# bbb_audio_decoder.net
KiCad netlist of a schematic drawn in EAGLE
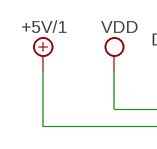
[diagram p0: schematic, sheet 1, part 1 of 2]
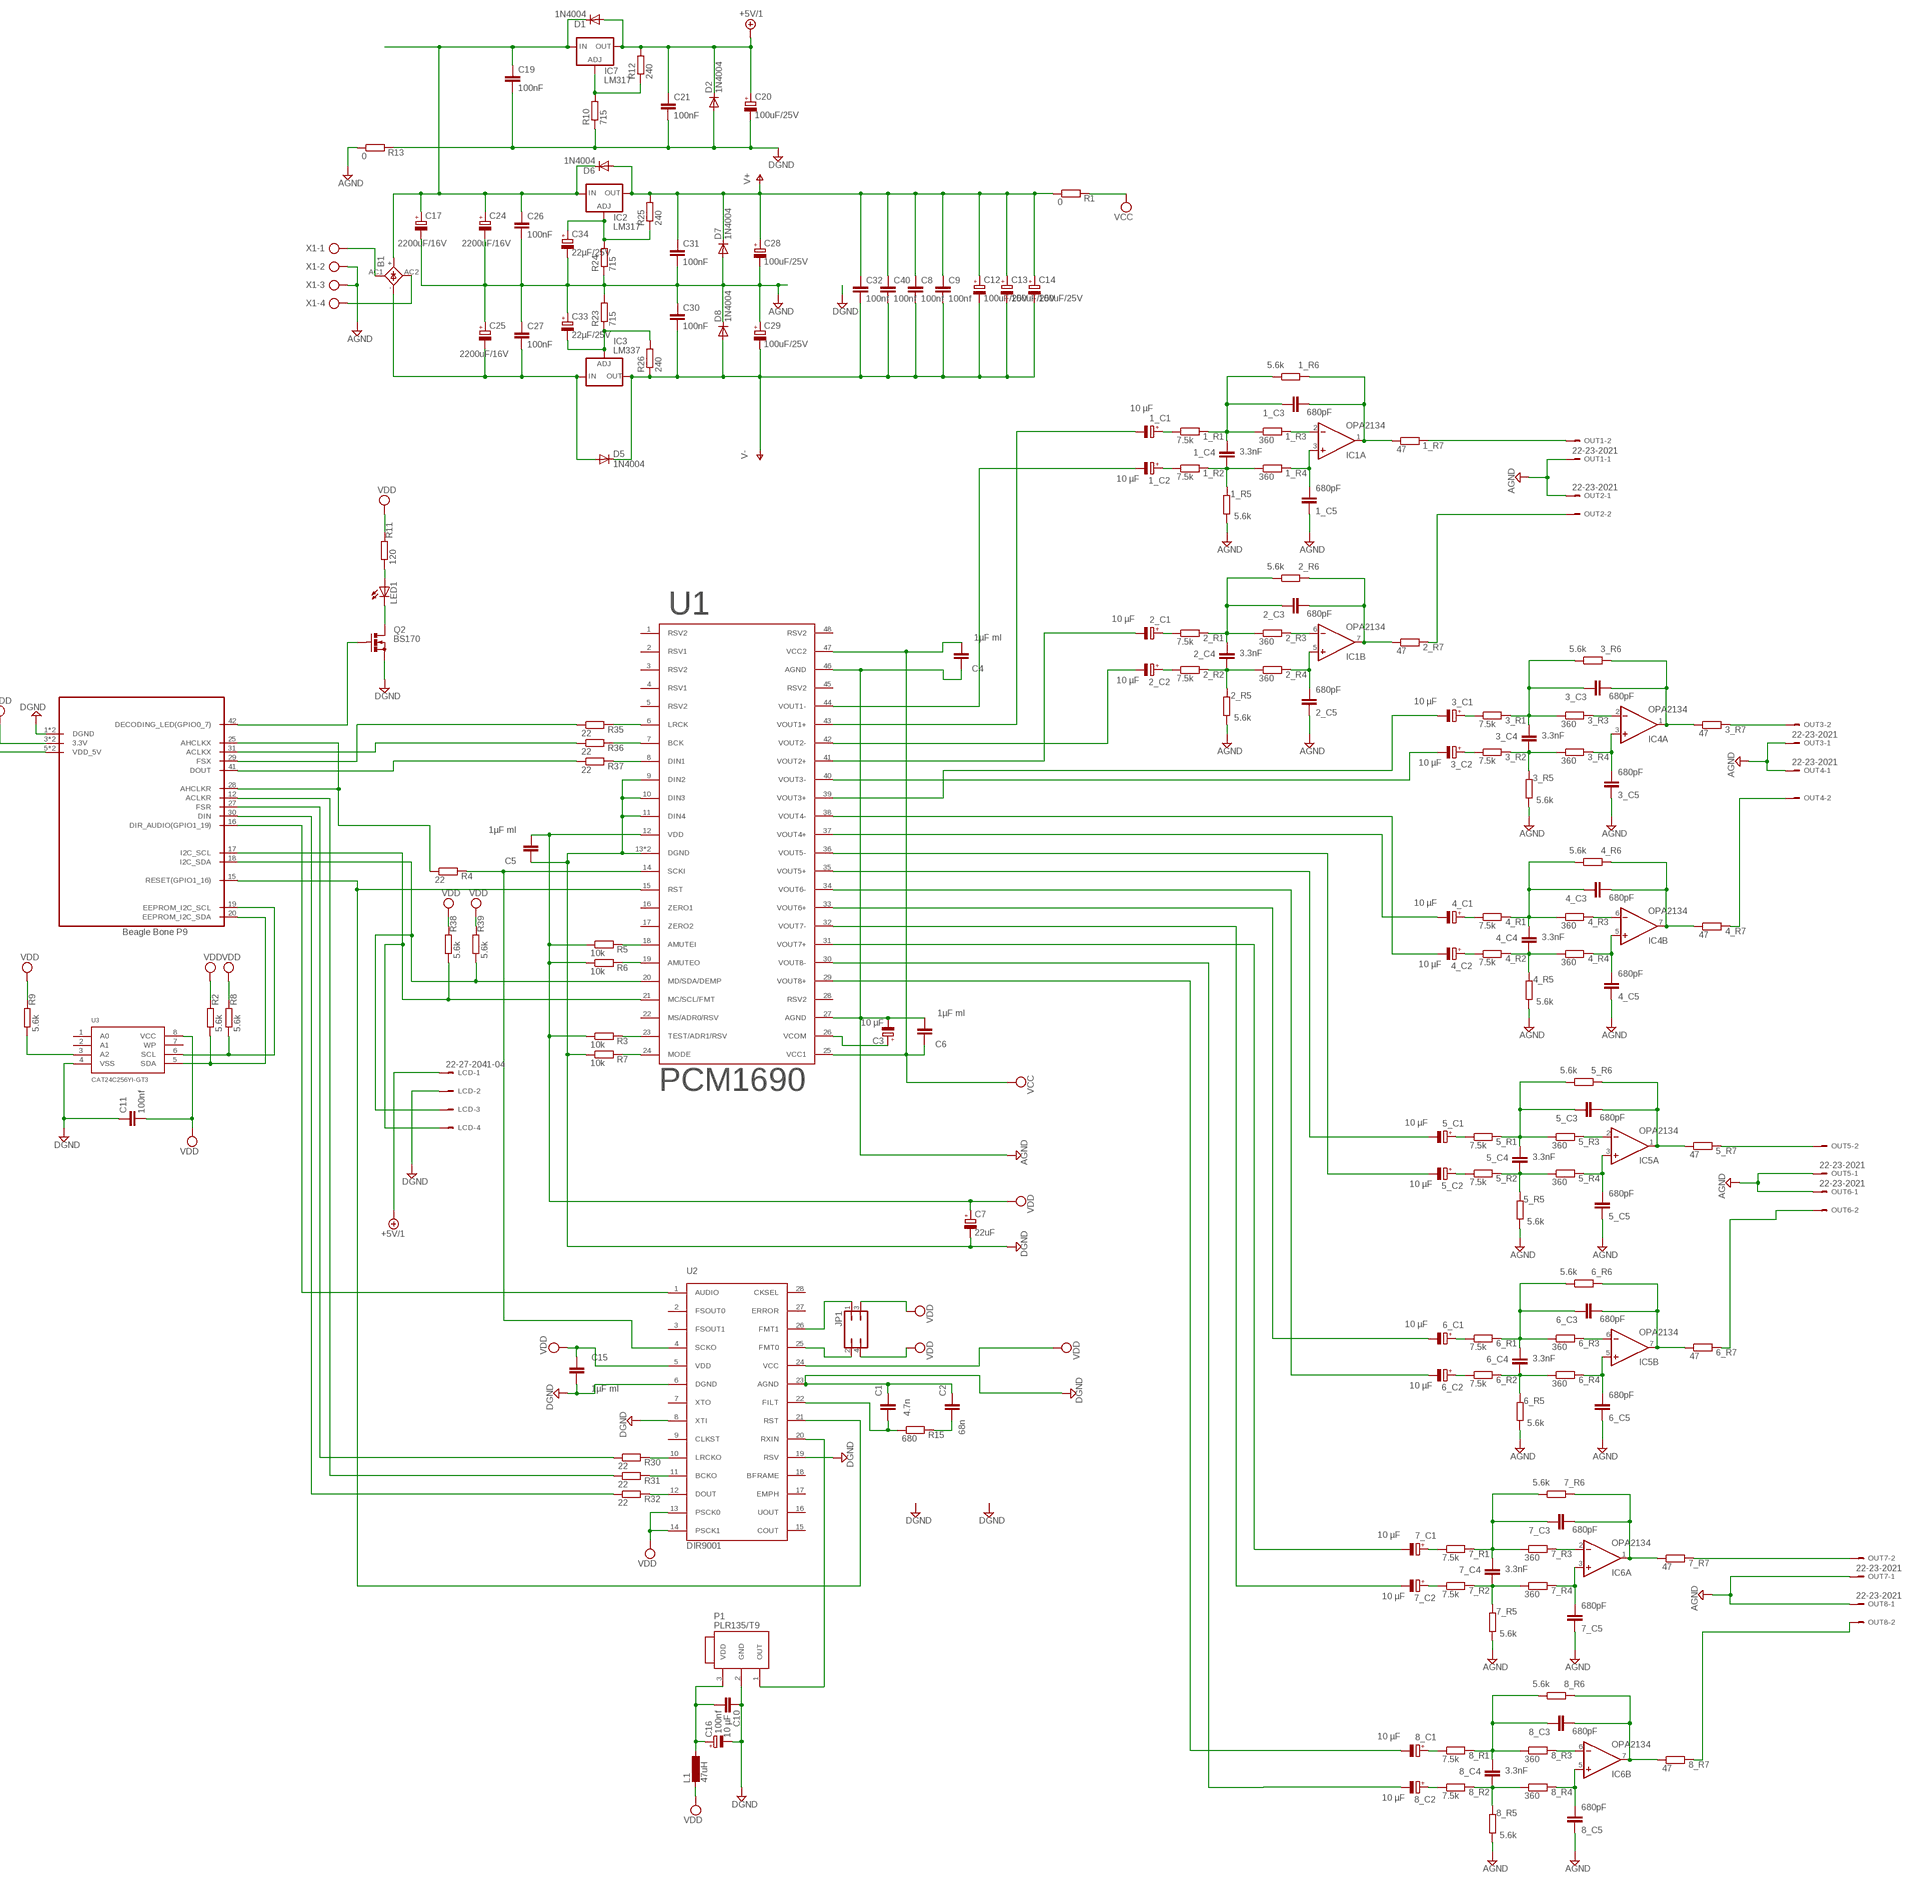
[diagram p1: schematic, sheet 1, part 2 of 2]

(export (version "E")
  (design (tool "Eeschema 10.0.6"))
  (components
    (comp (ref "1_C1")
      (value "10 µF")
      (footprint "eagle-import:E2-5")
      (libsource (lib "eagle-import") (part "CPOL-EUE2-5"))
    )
    (comp (ref "1_C2")
      (value "10 µF")
      (footprint "eagle-import:E2-5")
      (libsource (lib "eagle-import") (part "CPOL-EUE2-5"))
    )
    (comp (ref "1_C3")
      (value "680pF")
      (footprint "eagle-import:C050-024X044")
      (libsource (lib "eagle-import") (part "C-EU050-024X044"))
    )
    (comp (ref "1_C4")
      (value "3.3nF")
      (footprint "eagle-import:C050-025X075")
      (libsource (lib "eagle-import") (part "C-EU050-025X075"))
    )
    (comp (ref "1_C5")
      (value "680pF")
      (footprint "eagle-import:C050-024X044")
      (libsource (lib "eagle-import") (part "C-EU050-024X044"))
    )
    (comp (ref "1_R1")
      (value "7.5k")
      (footprint "eagle-import:0207_7")
      (libsource (lib "eagle-import") (part "R-EU_0207/7"))
    )
    (comp (ref "1_R2")
      (value "7.5k")
      (footprint "eagle-import:0207_7")
      (libsource (lib "eagle-import") (part "R-EU_0207/7"))
    )
    (comp (ref "1_R3")
      (value "360")
      (footprint "eagle-import:0207_7")
      (libsource (lib "eagle-import") (part "R-EU_0207/7"))
    )
    (comp (ref "1_R4")
      (value "360")
      (footprint "eagle-import:0207_7")
      (libsource (lib "eagle-import") (part "R-EU_0207/7"))
    )
    (comp (ref "1_R5")
      (value "5.6k")
      (footprint "eagle-import:0207_7")
      (libsource (lib "eagle-import") (part "R-EU_0207/7"))
    )
    (comp (ref "1_R6")
      (value "5.6k")
      (footprint "eagle-import:0207_7")
      (libsource (lib "eagle-import") (part "R-EU_0207/7"))
    )
    (comp (ref "1_R7")
      (value "47")
      (footprint "eagle-import:0207_7")
      (libsource (lib "eagle-import") (part "R-EU_0207/7"))
    )
    (comp (ref "2_C1")
      (value "10 µF")
      (footprint "eagle-import:E2-5")
      (libsource (lib "eagle-import") (part "CPOL-EUE2-5"))
    )
    (comp (ref "2_C2")
      (value "10 µF")
      (footprint "eagle-import:E2-5")
      (libsource (lib "eagle-import") (part "CPOL-EUE2-5"))
    )
    (comp (ref "2_C3")
      (value "680pF")
      (footprint "eagle-import:C050-024X044")
      (libsource (lib "eagle-import") (part "C-EU050-024X044"))
    )
    (comp (ref "2_C4")
      (value "3.3nF")
      (footprint "eagle-import:C050-025X075")
      (libsource (lib "eagle-import") (part "C-EU050-025X075"))
    )
    (comp (ref "2_C5")
      (value "680pF")
      (footprint "eagle-import:C050-024X044")
      (libsource (lib "eagle-import") (part "C-EU050-024X044"))
    )
    (comp (ref "2_R1")
      (value "7.5k")
      (footprint "eagle-import:0207_7")
      (libsource (lib "eagle-import") (part "R-EU_0207/7"))
    )
    (comp (ref "2_R2")
      (value "7.5k")
      (footprint "eagle-import:0207_7")
      (libsource (lib "eagle-import") (part "R-EU_0207/7"))
    )
    (comp (ref "2_R3")
      (value "360")
      (footprint "eagle-import:0207_7")
      (libsource (lib "eagle-import") (part "R-EU_0207/7"))
    )
    (comp (ref "2_R4")
      (value "360")
      (footprint "eagle-import:0207_7")
      (libsource (lib "eagle-import") (part "R-EU_0207/7"))
    )
    (comp (ref "2_R5")
      (value "5.6k")
      (footprint "eagle-import:0207_7")
      (libsource (lib "eagle-import") (part "R-EU_0207/7"))
    )
    (comp (ref "2_R6")
      (value "5.6k")
      (footprint "eagle-import:0207_7")
      (libsource (lib "eagle-import") (part "R-EU_0207/7"))
    )
    (comp (ref "2_R7")
      (value "47")
      (footprint "eagle-import:0207_7")
      (libsource (lib "eagle-import") (part "R-EU_0207/7"))
    )
    (comp (ref "3_C1")
      (value "10 µF")
      (footprint "eagle-import:E2-5")
      (libsource (lib "eagle-import") (part "CPOL-EUE2-5"))
    )
    (comp (ref "3_C2")
      (value "10 µF")
      (footprint "eagle-import:E2-5")
      (libsource (lib "eagle-import") (part "CPOL-EUE2-5"))
    )
    (comp (ref "3_C3")
      (value "680pF")
      (footprint "eagle-import:C050-024X044")
      (libsource (lib "eagle-import") (part "C-EU050-024X044"))
    )
    (comp (ref "3_C4")
      (value "3.3nF")
      (footprint "eagle-import:C050-025X075")
      (libsource (lib "eagle-import") (part "C-EU050-025X075"))
    )
    (comp (ref "3_C5")
      (value "680pF")
      (footprint "eagle-import:C050-024X044")
      (libsource (lib "eagle-import") (part "C-EU050-024X044"))
    )
    (comp (ref "3_R1")
      (value "7.5k")
      (footprint "eagle-import:0207_7")
      (libsource (lib "eagle-import") (part "R-EU_0207/7"))
    )
    (comp (ref "3_R2")
      (value "7.5k")
      (footprint "eagle-import:0207_7")
      (libsource (lib "eagle-import") (part "R-EU_0207/7"))
    )
    (comp (ref "3_R3")
      (value "360")
      (footprint "eagle-import:0207_7")
      (libsource (lib "eagle-import") (part "R-EU_0207/7"))
    )
    (comp (ref "3_R4")
      (value "360")
      (footprint "eagle-import:0207_7")
      (libsource (lib "eagle-import") (part "R-EU_0207/7"))
    )
    (comp (ref "3_R5")
      (value "5.6k")
      (footprint "eagle-import:0207_7")
      (libsource (lib "eagle-import") (part "R-EU_0207/7"))
    )
    (comp (ref "3_R6")
      (value "5.6k")
      (footprint "eagle-import:0207_7")
      (libsource (lib "eagle-import") (part "R-EU_0207/7"))
    )
    (comp (ref "3_R7")
      (value "47")
      (footprint "eagle-import:0207_7")
      (libsource (lib "eagle-import") (part "R-EU_0207/7"))
    )
    (comp (ref "4_C1")
      (value "10 µF")
      (footprint "eagle-import:E2-5")
      (libsource (lib "eagle-import") (part "CPOL-EUE2-5"))
    )
    (comp (ref "4_C2")
      (value "10 µF")
      (footprint "eagle-import:E2-5")
      (libsource (lib "eagle-import") (part "CPOL-EUE2-5"))
    )
    (comp (ref "4_C3")
      (value "680pF")
      (footprint "eagle-import:C050-024X044")
      (libsource (lib "eagle-import") (part "C-EU050-024X044"))
    )
    (comp (ref "4_C4")
      (value "3.3nF")
      (footprint "eagle-import:C050-025X075")
      (libsource (lib "eagle-import") (part "C-EU050-025X075"))
    )
    (comp (ref "4_C5")
      (value "680pF")
      (footprint "eagle-import:C050-024X044")
      (libsource (lib "eagle-import") (part "C-EU050-024X044"))
    )
    (comp (ref "4_R1")
      (value "7.5k")
      (footprint "eagle-import:0207_7")
      (libsource (lib "eagle-import") (part "R-EU_0207/7"))
    )
    (comp (ref "4_R2")
      (value "7.5k")
      (footprint "eagle-import:0207_7")
      (libsource (lib "eagle-import") (part "R-EU_0207/7"))
    )
    (comp (ref "4_R3")
      (value "360")
      (footprint "eagle-import:0207_7")
      (libsource (lib "eagle-import") (part "R-EU_0207/7"))
    )
    (comp (ref "4_R4")
      (value "360")
      (footprint "eagle-import:0207_7")
      (libsource (lib "eagle-import") (part "R-EU_0207/7"))
    )
    (comp (ref "4_R5")
      (value "5.6k")
      (footprint "eagle-import:0207_7")
      (libsource (lib "eagle-import") (part "R-EU_0207/7"))
    )
    (comp (ref "4_R6")
      (value "5.6k")
      (footprint "eagle-import:0207_7")
      (libsource (lib "eagle-import") (part "R-EU_0207/7"))
    )
    (comp (ref "4_R7")
      (value "47")
      (footprint "eagle-import:0207_7")
      (libsource (lib "eagle-import") (part "R-EU_0207/7"))
    )
    (comp (ref "5_C1")
      (value "10 µF")
      (footprint "eagle-import:E2-5")
      (libsource (lib "eagle-import") (part "CPOL-EUE2-5"))
    )
    (comp (ref "5_C2")
      (value "10 µF")
      (footprint "eagle-import:E2-5")
      (libsource (lib "eagle-import") (part "CPOL-EUE2-5"))
    )
    (comp (ref "5_C3")
      (value "680pF")
      (footprint "eagle-import:C050-024X044")
      (libsource (lib "eagle-import") (part "C-EU050-024X044"))
    )
    (comp (ref "5_C4")
      (value "3.3nF")
      (footprint "eagle-import:C050-025X075")
      (libsource (lib "eagle-import") (part "C-EU050-025X075"))
    )
    (comp (ref "5_C5")
      (value "680pF")
      (footprint "eagle-import:C050-024X044")
      (libsource (lib "eagle-import") (part "C-EU050-024X044"))
    )
    (comp (ref "5_R1")
      (value "7.5k")
      (footprint "eagle-import:0207_7")
      (libsource (lib "eagle-import") (part "R-EU_0207/7"))
    )
    (comp (ref "5_R2")
      (value "7.5k")
      (footprint "eagle-import:0207_7")
      (libsource (lib "eagle-import") (part "R-EU_0207/7"))
    )
    (comp (ref "5_R3")
      (value "360")
      (footprint "eagle-import:0207_7")
      (libsource (lib "eagle-import") (part "R-EU_0207/7"))
    )
    (comp (ref "5_R4")
      (value "360")
      (footprint "eagle-import:0207_7")
      (libsource (lib "eagle-import") (part "R-EU_0207/7"))
    )
    (comp (ref "5_R5")
      (value "5.6k")
      (footprint "eagle-import:0207_7")
      (libsource (lib "eagle-import") (part "R-EU_0207/7"))
    )
    (comp (ref "5_R6")
      (value "5.6k")
      (footprint "eagle-import:0207_7")
      (libsource (lib "eagle-import") (part "R-EU_0207/7"))
    )
    (comp (ref "5_R7")
      (value "47")
      (footprint "eagle-import:0207_7")
      (libsource (lib "eagle-import") (part "R-EU_0207/7"))
    )
    (comp (ref "6_C1")
      (value "10 µF")
      (footprint "eagle-import:E2-5")
      (libsource (lib "eagle-import") (part "CPOL-EUE2-5"))
    )
    (comp (ref "6_C2")
      (value "10 µF")
      (footprint "eagle-import:E2-5")
      (libsource (lib "eagle-import") (part "CPOL-EUE2-5"))
    )
    (comp (ref "6_C3")
      (value "680pF")
      (footprint "eagle-import:C050-024X044")
      (libsource (lib "eagle-import") (part "C-EU050-024X044"))
    )
    (comp (ref "6_C4")
      (value "3.3nF")
      (footprint "eagle-import:C050-025X075")
      (libsource (lib "eagle-import") (part "C-EU050-025X075"))
    )
    (comp (ref "6_C5")
      (value "680pF")
      (footprint "eagle-import:C050-024X044")
      (libsource (lib "eagle-import") (part "C-EU050-024X044"))
    )
    (comp (ref "6_R1")
      (value "7.5k")
      (footprint "eagle-import:0207_7")
      (libsource (lib "eagle-import") (part "R-EU_0207/7"))
    )
    (comp (ref "6_R2")
      (value "7.5k")
      (footprint "eagle-import:0207_7")
      (libsource (lib "eagle-import") (part "R-EU_0207/7"))
    )
    (comp (ref "6_R3")
      (value "360")
      (footprint "eagle-import:0207_7")
      (libsource (lib "eagle-import") (part "R-EU_0207/7"))
    )
    (comp (ref "6_R4")
      (value "360")
      (footprint "eagle-import:0207_7")
      (libsource (lib "eagle-import") (part "R-EU_0207/7"))
    )
    (comp (ref "6_R5")
      (value "5.6k")
      (footprint "eagle-import:0207_7")
      (libsource (lib "eagle-import") (part "R-EU_0207/7"))
    )
    (comp (ref "6_R6")
      (value "5.6k")
      (footprint "eagle-import:0207_7")
      (libsource (lib "eagle-import") (part "R-EU_0207/7"))
    )
    (comp (ref "6_R7")
      (value "47")
      (footprint "eagle-import:0207_7")
      (libsource (lib "eagle-import") (part "R-EU_0207/7"))
    )
    (comp (ref "7_C1")
      (value "10 µF")
      (footprint "eagle-import:E2-5")
      (libsource (lib "eagle-import") (part "CPOL-EUE2-5"))
    )
    (comp (ref "7_C2")
      (value "10 µF")
      (footprint "eagle-import:E2-5")
      (libsource (lib "eagle-import") (part "CPOL-EUE2-5"))
    )
    (comp (ref "7_C3")
      (value "680pF")
      (footprint "eagle-import:C050-024X044")
      (libsource (lib "eagle-import") (part "C-EU050-024X044"))
    )
    (comp (ref "7_C4")
      (value "3.3nF")
      (footprint "eagle-import:C050-025X075")
      (libsource (lib "eagle-import") (part "C-EU050-025X075"))
    )
    (comp (ref "7_C5")
      (value "680pF")
      (footprint "eagle-import:C050-024X044")
      (libsource (lib "eagle-import") (part "C-EU050-024X044"))
    )
    (comp (ref "7_R1")
      (value "7.5k")
      (footprint "eagle-import:0207_7")
      (libsource (lib "eagle-import") (part "R-EU_0207/7"))
    )
    (comp (ref "7_R2")
      (value "7.5k")
      (footprint "eagle-import:0207_7")
      (libsource (lib "eagle-import") (part "R-EU_0207/7"))
    )
    (comp (ref "7_R3")
      (value "360")
      (footprint "eagle-import:0207_7")
      (libsource (lib "eagle-import") (part "R-EU_0207/7"))
    )
    (comp (ref "7_R4")
      (value "360")
      (footprint "eagle-import:0207_7")
      (libsource (lib "eagle-import") (part "R-EU_0207/7"))
    )
    (comp (ref "7_R5")
      (value "5.6k")
      (footprint "eagle-import:0207_7")
      (libsource (lib "eagle-import") (part "R-EU_0207/7"))
    )
    (comp (ref "7_R6")
      (value "5.6k")
      (footprint "eagle-import:0207_7")
      (libsource (lib "eagle-import") (part "R-EU_0207/7"))
    )
    (comp (ref "7_R7")
      (value "47")
      (footprint "eagle-import:0207_7")
      (libsource (lib "eagle-import") (part "R-EU_0207/7"))
    )
    (comp (ref "8_C1")
      (value "10 µF")
      (footprint "eagle-import:E2-5")
      (libsource (lib "eagle-import") (part "CPOL-EUE2-5"))
    )
    (comp (ref "8_C2")
      (value "10 µF")
      (footprint "eagle-import:E2-5")
      (libsource (lib "eagle-import") (part "CPOL-EUE2-5"))
    )
    (comp (ref "8_C3")
      (value "680pF")
      (footprint "eagle-import:C050-024X044")
      (libsource (lib "eagle-import") (part "C-EU050-024X044"))
    )
    (comp (ref "8_C4")
      (value "3.3nF")
      (footprint "eagle-import:C050-025X075")
      (libsource (lib "eagle-import") (part "C-EU050-025X075"))
    )
    (comp (ref "8_C5")
      (value "680pF")
      (footprint "eagle-import:C050-024X044")
      (libsource (lib "eagle-import") (part "C-EU050-024X044"))
    )
    (comp (ref "8_R1")
      (value "7.5k")
      (footprint "eagle-import:0207_7")
      (libsource (lib "eagle-import") (part "R-EU_0207/7"))
    )
    (comp (ref "8_R2")
      (value "7.5k")
      (footprint "eagle-import:0207_7")
      (libsource (lib "eagle-import") (part "R-EU_0207/7"))
    )
    (comp (ref "8_R3")
      (value "360")
      (footprint "eagle-import:0207_7")
      (libsource (lib "eagle-import") (part "R-EU_0207/7"))
    )
    (comp (ref "8_R4")
      (value "360")
      (footprint "eagle-import:0207_7")
      (libsource (lib "eagle-import") (part "R-EU_0207/7"))
    )
    (comp (ref "8_R5")
      (value "5.6k")
      (footprint "eagle-import:0207_7")
      (libsource (lib "eagle-import") (part "R-EU_0207/7"))
    )
    (comp (ref "8_R6")
      (value "5.6k")
      (footprint "eagle-import:0207_7")
      (libsource (lib "eagle-import") (part "R-EU_0207/7"))
    )
    (comp (ref "8_R7")
      (value "47")
      (footprint "eagle-import:0207_7")
      (libsource (lib "eagle-import") (part "R-EU_0207/7"))
    )
    (comp (ref "B1")
      (value "FB15")
      (footprint "eagle-import:FB15")
      (libsource (lib "eagle-import") (part "FB15"))
    )
    (comp (ref "C1")
      (value "4.7n")
      (footprint "eagle-import:C050-024X044")
      (libsource (lib "eagle-import") (part "C-EU050-024X044"))
    )
    (comp (ref "C2")
      (value "68n")
      (footprint "eagle-import:C050-024X044")
      (libsource (lib "eagle-import") (part "C-EU050-024X044"))
    )
    (comp (ref "C3")
      (value "10 µF")
      (footprint "eagle-import:E2-5")
      (libsource (lib "eagle-import") (part "CPOL-EUE2-5"))
    )
    (comp (ref "C4")
      (value "1µF ml")
      (footprint "eagle-import:C050-024X044")
      (libsource (lib "eagle-import") (part "C-EU050-024X044"))
    )
    (comp (ref "C5")
      (value "1µF ml")
      (footprint "eagle-import:C050-024X044")
      (libsource (lib "eagle-import") (part "C-EU050-024X044"))
    )
    (comp (ref "C6")
      (value "1µF ml")
      (footprint "eagle-import:C050-024X044")
      (libsource (lib "eagle-import") (part "C-EU050-024X044"))
    )
    (comp (ref "C7")
      (value "22uF")
      (footprint "eagle-import:E2-5")
      (libsource (lib "eagle-import") (part "CPOL-EUE2-5"))
    )
    (comp (ref "C8")
      (value "100nf")
      (footprint "eagle-import:C050-024X044")
      (libsource (lib "eagle-import") (part "C-EU050-024X044"))
    )
    (comp (ref "C9")
      (value "100nf")
      (footprint "eagle-import:C050-024X044")
      (libsource (lib "eagle-import") (part "C-EU050-024X044"))
    )
    (comp (ref "C10")
      (value "100nf")
      (footprint "eagle-import:C050-024X044")
      (libsource (lib "eagle-import") (part "C-EU050-024X044"))
    )
    (comp (ref "C11")
      (value "100nf")
      (footprint "eagle-import:C050-024X044")
      (libsource (lib "eagle-import") (part "C-EU050-024X044"))
    )
    (comp (ref "C12")
      (value "100uF/25V")
      (footprint "eagle-import:E2,5-6")
      (libsource (lib "eagle-import") (part "CPOL-EUE2.5-6"))
    )
    (comp (ref "C13")
      (value "100uF/25V")
      (footprint "eagle-import:E2,5-6")
      (libsource (lib "eagle-import") (part "CPOL-EUE2.5-6"))
    )
    (comp (ref "C14")
      (value "100uF/25V")
      (footprint "eagle-import:E2,5-6")
      (libsource (lib "eagle-import") (part "CPOL-EUE2.5-6"))
    )
    (comp (ref "C15")
      (value "1µF ml")
      (footprint "eagle-import:C050-024X044")
      (libsource (lib "eagle-import") (part "C-EU050-024X044"))
    )
    (comp (ref "C16")
      (value "10 µF")
      (footprint "eagle-import:E2-5")
      (libsource (lib "eagle-import") (part "CPOL-EUE2-5"))
    )
    (comp (ref "C17")
      (value "2200uF/16V")
      (footprint "eagle-import:E5-13")
      (libsource (lib "eagle-import") (part "CPOL-EUE5-13"))
    )
    (comp (ref "C19")
      (value "100nF")
      (footprint "eagle-import:C050-024X044")
      (libsource (lib "eagle-import") (part "C-EU050-024X044"))
    )
    (comp (ref "C20")
      (value "100uF/25V")
      (footprint "eagle-import:E2,5-6")
      (libsource (lib "eagle-import") (part "CPOL-EUE2.5-6"))
    )
    (comp (ref "C21")
      (value "100nF")
      (footprint "eagle-import:C050-024X044")
      (libsource (lib "eagle-import") (part "C-EU050-024X044"))
    )
    (comp (ref "C24")
      (value "2200uF/16V")
      (footprint "eagle-import:E5-13")
      (libsource (lib "eagle-import") (part "CPOL-EUE5-13"))
    )
    (comp (ref "C25")
      (value "2200uF/16V")
      (footprint "eagle-import:E5-13")
      (libsource (lib "eagle-import") (part "CPOL-EUE5-13"))
    )
    (comp (ref "C26")
      (value "100nF")
      (footprint "eagle-import:C050-024X044")
      (libsource (lib "eagle-import") (part "C-EU050-024X044"))
    )
    (comp (ref "C27")
      (value "100nF")
      (footprint "eagle-import:C050-024X044")
      (libsource (lib "eagle-import") (part "C-EU050-024X044"))
    )
    (comp (ref "C28")
      (value "100uF/25V")
      (footprint "eagle-import:E2,5-6")
      (libsource (lib "eagle-import") (part "CPOL-EUE2.5-6"))
    )
    (comp (ref "C29")
      (value "100uF/25V")
      (footprint "eagle-import:E2,5-6")
      (libsource (lib "eagle-import") (part "CPOL-EUE2.5-6"))
    )
    (comp (ref "C30")
      (value "100nF")
      (footprint "eagle-import:C050-024X044")
      (libsource (lib "eagle-import") (part "C-EU050-024X044"))
    )
    (comp (ref "C31")
      (value "100nF")
      (footprint "eagle-import:C050-024X044")
      (libsource (lib "eagle-import") (part "C-EU050-024X044"))
    )
    (comp (ref "C32")
      (value "100nf")
      (footprint "eagle-import:C050-024X044")
      (libsource (lib "eagle-import") (part "C-EU050-024X044"))
    )
    (comp (ref "C33")
      (value "22µF/25V")
      (footprint "eagle-import:E2,5-6")
      (libsource (lib "eagle-import") (part "CPOL-EUE2.5-6"))
    )
    (comp (ref "C34")
      (value "22µF/25V")
      (footprint "eagle-import:E2,5-6")
      (libsource (lib "eagle-import") (part "CPOL-EUE2.5-6"))
    )
    (comp (ref "C40")
      (value "100nf")
      (footprint "eagle-import:C050-024X044")
      (libsource (lib "eagle-import") (part "C-EU050-024X044"))
    )
    (comp (ref "D1")
      (value "1N4004")
      (footprint "eagle-import:DO41-7.6")
      (libsource (lib "eagle-import") (part "DIODE-DO41-7.6"))
    )
    (comp (ref "D2")
      (value "1N4004")
      (footprint "eagle-import:DO41-7.6")
      (libsource (lib "eagle-import") (part "DIODE-DO41-7.6"))
    )
    (comp (ref "D5")
      (value "1N4004")
      (footprint "eagle-import:DO41-7.6")
      (libsource (lib "eagle-import") (part "DIODE-DO41-7.6"))
    )
    (comp (ref "D6")
      (value "1N4004")
      (footprint "eagle-import:DO41-7.6")
      (libsource (lib "eagle-import") (part "DIODE-DO41-7.6"))
    )
    (comp (ref "D7")
      (value "1N4004")
      (footprint "eagle-import:DO41-7.6")
      (libsource (lib "eagle-import") (part "DIODE-DO41-7.6"))
    )
    (comp (ref "D8")
      (value "1N4004")
      (footprint "eagle-import:DO41-7.6")
      (libsource (lib "eagle-import") (part "DIODE-DO41-7.6"))
    )
    (comp (ref "IC1")
      (value "OPA2134")
      (footprint "eagle-import:DIL8")
      (libsource (lib "eagle-import") (part "TL072P"))
    )
    (comp (ref "IC2")
      (value "LM317")
      (footprint "eagle-import:317TS")
      (libsource (lib "eagle-import") (part "LM317TS"))
    )
    (comp (ref "IC3")
      (value "LM337")
      (footprint "eagle-import:337TS")
      (libsource (lib "eagle-import") (part "LM337TS"))
    )
    (comp (ref "IC4")
      (value "OPA2134")
      (footprint "eagle-import:DIL8")
      (libsource (lib "eagle-import") (part "TL072P"))
    )
    (comp (ref "IC5")
      (value "OPA2134")
      (footprint "eagle-import:DIL8")
      (libsource (lib "eagle-import") (part "TL072P"))
    )
    (comp (ref "IC6")
      (value "OPA2134")
      (footprint "eagle-import:DIL8")
      (libsource (lib "eagle-import") (part "TL072P"))
    )
    (comp (ref "IC7")
      (value "LM317")
      (footprint "eagle-import:317TS")
      (libsource (lib "eagle-import") (part "LM317TS"))
    )
    (comp (ref "JP1")
      (value "JP2Q")
      (footprint "eagle-import:JP2Q")
      (libsource (lib "eagle-import") (part "JP2Q"))
    )
    (comp (ref "L1")
      (value "47uH")
      (footprint "eagle-import:0207_10")
      (libsource (lib "eagle-import") (part "L-EU0207/10"))
    )
    (comp (ref "LCD")
      (value "22-27-2041-04")
      (footprint "eagle-import:6410-04")
      (libsource (lib "eagle-import") (part "22-?-0427-2041"))
    )
    (comp (ref "LED1")
      (value "LEDSMT1206")
      (footprint "eagle-import:1206")
      (libsource (lib "eagle-import") (part "LEDSMT1206"))
    )
    (comp (ref "OUT1")
      (value "22-23-2021")
      (footprint "eagle-import:22-23-2021")
      (fields (field (name "MF") "MOLEX"))
      (libsource (lib "eagle-import") (part "22-23-2021"))
    )
    (comp (ref "OUT2")
      (value "22-23-2021")
      (footprint "eagle-import:22-23-2021")
      (fields (field (name "MF") "MOLEX"))
      (libsource (lib "eagle-import") (part "22-23-2021"))
    )
    (comp (ref "OUT3")
      (value "22-23-2021")
      (footprint "eagle-import:22-23-2021")
      (fields (field (name "MF") "MOLEX"))
      (libsource (lib "eagle-import") (part "22-23-2021"))
    )
    (comp (ref "OUT4")
      (value "22-23-2021")
      (footprint "eagle-import:22-23-2021")
      (fields (field (name "MF") "MOLEX"))
      (libsource (lib "eagle-import") (part "22-23-2021"))
    )
    (comp (ref "OUT5")
      (value "22-23-2021")
      (footprint "eagle-import:22-23-2021")
      (fields (field (name "MF") "MOLEX"))
      (libsource (lib "eagle-import") (part "22-23-2021"))
    )
    (comp (ref "OUT6")
      (value "22-23-2021")
      (footprint "eagle-import:22-23-2021")
      (fields (field (name "MF") "MOLEX"))
      (libsource (lib "eagle-import") (part "22-23-2021"))
    )
    (comp (ref "OUT7")
      (value "22-23-2021")
      (footprint "eagle-import:22-23-2021")
      (fields (field (name "MF") "MOLEX"))
      (libsource (lib "eagle-import") (part "22-23-2021"))
    )
    (comp (ref "OUT8")
      (value "22-23-2021")
      (footprint "eagle-import:22-23-2021")
      (fields (field (name "MF") "MOLEX"))
      (libsource (lib "eagle-import") (part "22-23-2021"))
    )
    (comp (ref "P1")
      (value "PLR135/T9")
      (footprint "eagle-import:PLR135_T9")
      (libsource (lib "eagle-import") (part "PLR135/T9"))
    )
    (comp (ref "Q2")
      (value "BS170")
      (footprint "eagle-import:SOT54E")
      (libsource (lib "eagle-import") (part "BS170"))
    )
    (comp (ref "R1")
      (value "0")
      (footprint "eagle-import:0204V")
      (libsource (lib "eagle-import") (part "R-EU_0204/2V"))
    )
    (comp (ref "R2")
      (value "5.6k")
      (footprint "eagle-import:0207_7")
      (libsource (lib "eagle-import") (part "R-EU_0207/7"))
    )
    (comp (ref "R3")
      (value "10k")
      (footprint "eagle-import:0207_7")
      (libsource (lib "eagle-import") (part "R-EU_0207/7"))
    )
    (comp (ref "R4")
      (value "22")
      (footprint "eagle-import:0207_7")
      (libsource (lib "eagle-import") (part "R-EU_0207/7"))
    )
    (comp (ref "R5")
      (value "10k")
      (footprint "eagle-import:0207_7")
      (libsource (lib "eagle-import") (part "R-EU_0207/7"))
    )
    (comp (ref "R6")
      (value "10k")
      (footprint "eagle-import:0207_7")
      (libsource (lib "eagle-import") (part "R-EU_0207/7"))
    )
    (comp (ref "R7")
      (value "10k")
      (footprint "eagle-import:0207_7")
      (libsource (lib "eagle-import") (part "R-EU_0207/7"))
    )
    (comp (ref "R8")
      (value "5.6k")
      (footprint "eagle-import:0207_7")
      (libsource (lib "eagle-import") (part "R-EU_0207/7"))
    )
    (comp (ref "R9")
      (value "5.6k")
      (footprint "eagle-import:0207_7")
      (libsource (lib "eagle-import") (part "R-EU_0207/7"))
    )
    (comp (ref "R10")
      (value "715")
      (footprint "eagle-import:0204V")
      (libsource (lib "eagle-import") (part "R-EU_0204/2V"))
    )
    (comp (ref "R11")
      (value "120")
      (footprint "eagle-import:0204V")
      (libsource (lib "eagle-import") (part "R-EU_0204/2V"))
    )
    (comp (ref "R12")
      (value "240")
      (footprint "eagle-import:0204V")
      (libsource (lib "eagle-import") (part "R-EU_0204/2V"))
    )
    (comp (ref "R13")
      (value "0")
      (footprint "eagle-import:0204V")
      (libsource (lib "eagle-import") (part "R-EU_0204/2V"))
    )
    (comp (ref "R15")
      (value "680")
      (footprint "eagle-import:0207_7")
      (libsource (lib "eagle-import") (part "R-EU_0207/7"))
    )
    (comp (ref "R23")
      (value "715")
      (footprint "eagle-import:0204V")
      (libsource (lib "eagle-import") (part "R-EU_0204/2V"))
    )
    (comp (ref "R24")
      (value "715")
      (footprint "eagle-import:0207_10")
      (libsource (lib "eagle-import") (part "R-EU_0207/10"))
    )
    (comp (ref "R25")
      (value "240")
      (footprint "eagle-import:0204V")
      (libsource (lib "eagle-import") (part "R-EU_0204/2V"))
    )
    (comp (ref "R26")
      (value "240")
      (footprint "eagle-import:0204V")
      (libsource (lib "eagle-import") (part "R-EU_0204/2V"))
    )
    (comp (ref "R30")
      (value "22")
      (footprint "eagle-import:0207_7")
      (libsource (lib "eagle-import") (part "R-EU_0207/7"))
    )
    (comp (ref "R31")
      (value "22")
      (footprint "eagle-import:0207_7")
      (libsource (lib "eagle-import") (part "R-EU_0207/7"))
    )
    (comp (ref "R32")
      (value "22")
      (footprint "eagle-import:0207_7")
      (libsource (lib "eagle-import") (part "R-EU_0207/7"))
    )
    (comp (ref "R35")
      (value "22")
      (footprint "eagle-import:0207_7")
      (libsource (lib "eagle-import") (part "R-EU_0207/7"))
    )
    (comp (ref "R36")
      (value "22")
      (footprint "eagle-import:0207_7")
      (libsource (lib "eagle-import") (part "R-EU_0207/7"))
    )
    (comp (ref "R37")
      (value "22")
      (footprint "eagle-import:0207_7")
      (libsource (lib "eagle-import") (part "R-EU_0207/7"))
    )
    (comp (ref "R38")
      (value "5.6k")
      (footprint "eagle-import:0207_7")
      (libsource (lib "eagle-import") (part "R-EU_0207/7"))
    )
    (comp (ref "R39")
      (value "5.6k")
      (footprint "eagle-import:0207_7")
      (libsource (lib "eagle-import") (part "R-EU_0207/7"))
    )
    (comp (ref "U$1")
      (value "BEAGLEBONEP9")
      (footprint "eagle-import:HEADERS23-2")
      (libsource (lib "eagle-import") (part "BEAGLEBONEP9"))
    )
    (comp (ref "U1")
      (value "PCM1690")
      (footprint "eagle-import:HTSSOP48DFD")
      (libsource (lib "eagle-import") (part "PCM1690"))
    )
    (comp (ref "U2")
      (value "DIR9001")
      (footprint "eagle-import:TSSOP28")
      (libsource (lib "eagle-import") (part "DIR9001"))
    )
    (comp (ref "U3")
      (value "CAT24C256YI-GT3")
      (footprint "eagle-import:TSSOP8")
      (libsource (lib "eagle-import") (part "CAT24C256YI-GT3"))
    )
    (comp (ref "X1")
      (value "AK500/4")
      (footprint "eagle-import:AK500_4")
      (libsource (lib "eagle-import") (part "AK500/4"))
    )
  )
  (nets
    (net (code "1") (name "+5V{slash}1") (class "Default")
      (node (ref "C20") (pin "+") (pinfunction "+_+") (pintype "passive"))
      (node (ref "C21") (pin "1") (pinfunction "1_1") (pintype "passive"))
      (node (ref "D1") (pin "A") (pinfunction "A_A") (pintype "passive"))
      (node (ref "D2") (pin "C") (pinfunction "C_C") (pintype "passive"))
      (node (ref "IC7") (pin "2") (pinfunction "OUT_2") (pintype "passive"))
      (node (ref "LCD") (pin "1") (pinfunction "S_1") (pintype "passive"))
      (node (ref "R12") (pin "2") (pinfunction "2_2") (pintype "passive"))
      (node (ref "U$1") (pin "5") (pinfunction "VDD_5V_5") (pintype "power_in"))
      (node (ref "U$1") (pin "6") (pinfunction "VDD_5V_6") (pintype "power_in"))
    )
    (net (code "2") (name "AGND") (class "Default")
      (node (ref "1_C5") (pin "1") (pinfunction "1_1") (pintype "passive"))
      (node (ref "1_R5") (pin "1") (pinfunction "1_1") (pintype "passive"))
      (node (ref "2_C5") (pin "1") (pinfunction "1_1") (pintype "passive"))
      (node (ref "2_R5") (pin "1") (pinfunction "1_1") (pintype "passive"))
      (node (ref "3_C5") (pin "1") (pinfunction "1_1") (pintype "passive"))
      (node (ref "3_R5") (pin "1") (pinfunction "1_1") (pintype "passive"))
      (node (ref "4_C5") (pin "1") (pinfunction "1_1") (pintype "passive"))
      (node (ref "4_R5") (pin "1") (pinfunction "1_1") (pintype "passive"))
      (node (ref "5_C5") (pin "1") (pinfunction "1_1") (pintype "passive"))
      (node (ref "5_R5") (pin "1") (pinfunction "1_1") (pintype "passive"))
      (node (ref "6_C5") (pin "1") (pinfunction "1_1") (pintype "passive"))
      (node (ref "6_R5") (pin "1") (pinfunction "1_1") (pintype "passive"))
      (node (ref "7_C5") (pin "1") (pinfunction "1_1") (pintype "passive"))
      (node (ref "7_R5") (pin "1") (pinfunction "1_1") (pintype "passive"))
      (node (ref "8_C5") (pin "1") (pinfunction "1_1") (pintype "passive"))
      (node (ref "8_R5") (pin "1") (pinfunction "1_1") (pintype "passive"))
      (node (ref "C17") (pin "-") (pinfunction "-_-") (pintype "passive"))
      (node (ref "C24") (pin "-") (pinfunction "-_-") (pintype "passive"))
      (node (ref "C25") (pin "+") (pinfunction "+_+") (pintype "passive"))
      (node (ref "C26") (pin "2") (pinfunction "2_2") (pintype "passive"))
      (node (ref "C27") (pin "1") (pinfunction "1_1") (pintype "passive"))
      (node (ref "C28") (pin "-") (pinfunction "-_-") (pintype "passive"))
      (node (ref "C29") (pin "+") (pinfunction "+_+") (pintype "passive"))
      (node (ref "C3") (pin "-") (pinfunction "-_-") (pintype "passive"))
      (node (ref "C30") (pin "1") (pinfunction "1_1") (pintype "passive"))
      (node (ref "C31") (pin "2") (pinfunction "2_2") (pintype "passive"))
      (node (ref "C33") (pin "+") (pinfunction "+_+") (pintype "passive"))
      (node (ref "C34") (pin "-") (pinfunction "-_-") (pintype "passive"))
      (node (ref "C4") (pin "1") (pinfunction "1_1") (pintype "passive"))
      (node (ref "C6") (pin "2") (pinfunction "2_2") (pintype "passive"))
      (node (ref "D7") (pin "A") (pinfunction "A_A") (pintype "passive"))
      (node (ref "D8") (pin "C") (pinfunction "C_C") (pintype "passive"))
      (node (ref "OUT1") (pin "1") (pinfunction "S_1") (pintype "passive"))
      (node (ref "OUT2") (pin "1") (pinfunction "S_1") (pintype "passive"))
      (node (ref "OUT3") (pin "1") (pinfunction "S_1") (pintype "passive"))
      (node (ref "OUT4") (pin "1") (pinfunction "S_1") (pintype "passive"))
      (node (ref "OUT5") (pin "1") (pinfunction "S_1") (pintype "passive"))
      (node (ref "OUT6") (pin "1") (pinfunction "S_1") (pintype "passive"))
      (node (ref "OUT7") (pin "1") (pinfunction "S_1") (pintype "passive"))
      (node (ref "OUT8") (pin "1") (pinfunction "S_1") (pintype "passive"))
      (node (ref "R13") (pin "1") (pinfunction "1_1") (pintype "passive"))
      (node (ref "R23") (pin "2") (pinfunction "2_2") (pintype "passive"))
      (node (ref "R24") (pin "1") (pinfunction "1_1") (pintype "passive"))
      (node (ref "U1") (pin "27") (pinfunction "AGND_27") (pintype "power_in"))
      (node (ref "U1") (pin "46") (pinfunction "AGND_46") (pintype "power_in"))
      (node (ref "X1") (pin "2") (pinfunction "KL_2") (pintype "passive"))
      (node (ref "X1") (pin "3") (pinfunction "KL_3") (pintype "passive"))
    )
    (net (code "3") (name "DGND") (class "Default")
      (node (ref "C1") (pin "1") (pinfunction "1_1") (pintype "passive"))
      (node (ref "C10") (pin "1") (pinfunction "1_1") (pintype "passive"))
      (node (ref "C11") (pin "1") (pinfunction "1_1") (pintype "passive"))
      (node (ref "C15") (pin "2") (pinfunction "2_2") (pintype "passive"))
      (node (ref "C16") (pin "-") (pinfunction "-_-") (pintype "passive"))
      (node (ref "C19") (pin "2") (pinfunction "2_2") (pintype "passive"))
      (node (ref "C2") (pin "1") (pinfunction "1_1") (pintype "passive"))
      (node (ref "C20") (pin "-") (pinfunction "-_-") (pintype "passive"))
      (node (ref "C21") (pin "2") (pinfunction "2_2") (pintype "passive"))
      (node (ref "C5") (pin "1") (pinfunction "1_1") (pintype "passive"))
      (node (ref "C7") (pin "-") (pinfunction "-_-") (pintype "passive"))
      (node (ref "D2") (pin "A") (pinfunction "A_A") (pintype "passive"))
      (node (ref "LCD") (pin "2") (pinfunction "S_2") (pintype "passive"))
      (node (ref "P1") (pin "2") (pinfunction "GND_2") (pintype "power_in"))
      (node (ref "Q2") (pin "S") (pinfunction "S_S") (pintype "passive"))
      (node (ref "R10") (pin "1") (pinfunction "1_1") (pintype "passive"))
      (node (ref "R13") (pin "2") (pinfunction "2_2") (pintype "passive"))
      (node (ref "R7") (pin "1") (pinfunction "1_1") (pintype "passive"))
      (node (ref "U$1") (pin "1") (pinfunction "DGND_1") (pintype "power_in"))
      (node (ref "U$1") (pin "2") (pinfunction "DGND_2") (pintype "power_in"))
      (node (ref "U1") (pin "10") (pinfunction "DIN3_10") (pintype "input"))
      (node (ref "U1") (pin "11") (pinfunction "DIN4_11") (pintype "input"))
      (node (ref "U1") (pin "13") (pinfunction "DGND_13") (pintype "power_in"))
      (node (ref "U1") (pin "9") (pinfunction "DIN2_9") (pintype "input"))
      (node (ref "U1") (pin "EXP") (pinfunction "DGND_EXP") (pintype "power_in"))
      (node (ref "U2") (pin "19") (pinfunction "RSV_19") (pintype "bidirectional"))
      (node (ref "U2") (pin "23") (pinfunction "AGND_23") (pintype "power_in"))
      (node (ref "U2") (pin "6") (pinfunction "DGND_6") (pintype "power_in"))
      (node (ref "U2") (pin "8") (pinfunction "XTI_8") (pintype "input"))
      (node (ref "U3") (pin "4") (pinfunction "VSS_4") (pintype "power_in"))
    )
    (net (code "4") (name "Net-(1_C1-Pad+)") (class "Default")
      (node (ref "1_C1") (pin "+") (pinfunction "+_+") (pintype "passive"))
      (node (ref "1_R1") (pin "1") (pinfunction "1_1") (pintype "passive"))
    )
    (net (code "5") (name "Net-(1_C2-Pad+)") (class "Default")
      (node (ref "1_C2") (pin "+") (pinfunction "+_+") (pintype "passive"))
      (node (ref "1_R2") (pin "1") (pinfunction "1_1") (pintype "passive"))
    )
    (net (code "6") (name "Net-(1_C3-Pad1)") (class "Default")
      (node (ref "1_C3") (pin "1") (pinfunction "1_1") (pintype "passive"))
      (node (ref "1_C4") (pin "2") (pinfunction "2_2") (pintype "passive"))
      (node (ref "1_R1") (pin "2") (pinfunction "2_2") (pintype "passive"))
      (node (ref "1_R3") (pin "1") (pinfunction "1_1") (pintype "passive"))
      (node (ref "1_R6") (pin "1") (pinfunction "1_1") (pintype "passive"))
    )
    (net (code "7") (name "Net-(1_C4-Pad1)") (class "Default")
      (node (ref "1_C4") (pin "1") (pinfunction "1_1") (pintype "passive"))
      (node (ref "1_R2") (pin "2") (pinfunction "2_2") (pintype "passive"))
      (node (ref "1_R4") (pin "1") (pinfunction "1_1") (pintype "passive"))
      (node (ref "1_R5") (pin "2") (pinfunction "2_2") (pintype "passive"))
    )
    (net (code "8") (name "Net-(2_C1-Pad+)") (class "Default")
      (node (ref "2_C1") (pin "+") (pinfunction "+_+") (pintype "passive"))
      (node (ref "2_R1") (pin "1") (pinfunction "1_1") (pintype "passive"))
    )
    (net (code "9") (name "Net-(2_C2-Pad+)") (class "Default")
      (node (ref "2_C2") (pin "+") (pinfunction "+_+") (pintype "passive"))
      (node (ref "2_R2") (pin "1") (pinfunction "1_1") (pintype "passive"))
    )
    (net (code "10") (name "Net-(2_C3-Pad1)") (class "Default")
      (node (ref "2_C3") (pin "1") (pinfunction "1_1") (pintype "passive"))
      (node (ref "2_C4") (pin "2") (pinfunction "2_2") (pintype "passive"))
      (node (ref "2_R1") (pin "2") (pinfunction "2_2") (pintype "passive"))
      (node (ref "2_R3") (pin "1") (pinfunction "1_1") (pintype "passive"))
      (node (ref "2_R6") (pin "1") (pinfunction "1_1") (pintype "passive"))
    )
    (net (code "11") (name "Net-(2_C4-Pad1)") (class "Default")
      (node (ref "2_C4") (pin "1") (pinfunction "1_1") (pintype "passive"))
      (node (ref "2_R2") (pin "2") (pinfunction "2_2") (pintype "passive"))
      (node (ref "2_R4") (pin "1") (pinfunction "1_1") (pintype "passive"))
      (node (ref "2_R5") (pin "2") (pinfunction "2_2") (pintype "passive"))
    )
    (net (code "12") (name "Net-(3_C1-Pad+)") (class "Default")
      (node (ref "3_C1") (pin "+") (pinfunction "+_+") (pintype "passive"))
      (node (ref "3_R1") (pin "1") (pinfunction "1_1") (pintype "passive"))
    )
    (net (code "13") (name "Net-(3_C2-Pad+)") (class "Default")
      (node (ref "3_C2") (pin "+") (pinfunction "+_+") (pintype "passive"))
      (node (ref "3_R2") (pin "1") (pinfunction "1_1") (pintype "passive"))
    )
    (net (code "14") (name "Net-(3_C3-Pad1)") (class "Default")
      (node (ref "3_C3") (pin "1") (pinfunction "1_1") (pintype "passive"))
      (node (ref "3_C4") (pin "2") (pinfunction "2_2") (pintype "passive"))
      (node (ref "3_R1") (pin "2") (pinfunction "2_2") (pintype "passive"))
      (node (ref "3_R3") (pin "1") (pinfunction "1_1") (pintype "passive"))
      (node (ref "3_R6") (pin "1") (pinfunction "1_1") (pintype "passive"))
    )
    (net (code "15") (name "Net-(3_C4-Pad1)") (class "Default")
      (node (ref "3_C4") (pin "1") (pinfunction "1_1") (pintype "passive"))
      (node (ref "3_R2") (pin "2") (pinfunction "2_2") (pintype "passive"))
      (node (ref "3_R4") (pin "1") (pinfunction "1_1") (pintype "passive"))
      (node (ref "3_R5") (pin "2") (pinfunction "2_2") (pintype "passive"))
    )
    (net (code "16") (name "Net-(4_C1-Pad+)") (class "Default")
      (node (ref "4_C1") (pin "+") (pinfunction "+_+") (pintype "passive"))
      (node (ref "4_R1") (pin "1") (pinfunction "1_1") (pintype "passive"))
    )
    (net (code "17") (name "Net-(4_C2-Pad+)") (class "Default")
      (node (ref "4_C2") (pin "+") (pinfunction "+_+") (pintype "passive"))
      (node (ref "4_R2") (pin "1") (pinfunction "1_1") (pintype "passive"))
    )
    (net (code "18") (name "Net-(4_C3-Pad1)") (class "Default")
      (node (ref "4_C3") (pin "1") (pinfunction "1_1") (pintype "passive"))
      (node (ref "4_C4") (pin "2") (pinfunction "2_2") (pintype "passive"))
      (node (ref "4_R1") (pin "2") (pinfunction "2_2") (pintype "passive"))
      (node (ref "4_R3") (pin "1") (pinfunction "1_1") (pintype "passive"))
      (node (ref "4_R6") (pin "1") (pinfunction "1_1") (pintype "passive"))
    )
    (net (code "19") (name "Net-(4_C4-Pad1)") (class "Default")
      (node (ref "4_C4") (pin "1") (pinfunction "1_1") (pintype "passive"))
      (node (ref "4_R2") (pin "2") (pinfunction "2_2") (pintype "passive"))
      (node (ref "4_R4") (pin "1") (pinfunction "1_1") (pintype "passive"))
      (node (ref "4_R5") (pin "2") (pinfunction "2_2") (pintype "passive"))
    )
    (net (code "20") (name "Net-(5_C1-Pad+)") (class "Default")
      (node (ref "5_C1") (pin "+") (pinfunction "+_+") (pintype "passive"))
      (node (ref "5_R1") (pin "1") (pinfunction "1_1") (pintype "passive"))
    )
    (net (code "21") (name "Net-(5_C2-Pad+)") (class "Default")
      (node (ref "5_C2") (pin "+") (pinfunction "+_+") (pintype "passive"))
      (node (ref "5_R2") (pin "1") (pinfunction "1_1") (pintype "passive"))
    )
    (net (code "22") (name "Net-(5_C3-Pad1)") (class "Default")
      (node (ref "5_C3") (pin "1") (pinfunction "1_1") (pintype "passive"))
      (node (ref "5_C4") (pin "2") (pinfunction "2_2") (pintype "passive"))
      (node (ref "5_R1") (pin "2") (pinfunction "2_2") (pintype "passive"))
      (node (ref "5_R3") (pin "1") (pinfunction "1_1") (pintype "passive"))
      (node (ref "5_R6") (pin "1") (pinfunction "1_1") (pintype "passive"))
    )
    (net (code "23") (name "Net-(5_C4-Pad1)") (class "Default")
      (node (ref "5_C4") (pin "1") (pinfunction "1_1") (pintype "passive"))
      (node (ref "5_R2") (pin "2") (pinfunction "2_2") (pintype "passive"))
      (node (ref "5_R4") (pin "1") (pinfunction "1_1") (pintype "passive"))
      (node (ref "5_R5") (pin "2") (pinfunction "2_2") (pintype "passive"))
    )
    (net (code "24") (name "Net-(6_C1-Pad+)") (class "Default")
      (node (ref "6_C1") (pin "+") (pinfunction "+_+") (pintype "passive"))
      (node (ref "6_R1") (pin "1") (pinfunction "1_1") (pintype "passive"))
    )
    (net (code "25") (name "Net-(6_C2-Pad+)") (class "Default")
      (node (ref "6_C2") (pin "+") (pinfunction "+_+") (pintype "passive"))
      (node (ref "6_R2") (pin "1") (pinfunction "1_1") (pintype "passive"))
    )
    (net (code "26") (name "Net-(6_C3-Pad1)") (class "Default")
      (node (ref "6_C3") (pin "1") (pinfunction "1_1") (pintype "passive"))
      (node (ref "6_C4") (pin "2") (pinfunction "2_2") (pintype "passive"))
      (node (ref "6_R1") (pin "2") (pinfunction "2_2") (pintype "passive"))
      (node (ref "6_R3") (pin "1") (pinfunction "1_1") (pintype "passive"))
      (node (ref "6_R6") (pin "1") (pinfunction "1_1") (pintype "passive"))
    )
    (net (code "27") (name "Net-(6_C4-Pad1)") (class "Default")
      (node (ref "6_C4") (pin "1") (pinfunction "1_1") (pintype "passive"))
      (node (ref "6_R2") (pin "2") (pinfunction "2_2") (pintype "passive"))
      (node (ref "6_R4") (pin "1") (pinfunction "1_1") (pintype "passive"))
      (node (ref "6_R5") (pin "2") (pinfunction "2_2") (pintype "passive"))
    )
    (net (code "28") (name "Net-(7_C1-Pad+)") (class "Default")
      (node (ref "7_C1") (pin "+") (pinfunction "+_+") (pintype "passive"))
      (node (ref "7_R1") (pin "1") (pinfunction "1_1") (pintype "passive"))
    )
    (net (code "29") (name "Net-(7_C2-Pad+)") (class "Default")
      (node (ref "7_C2") (pin "+") (pinfunction "+_+") (pintype "passive"))
      (node (ref "7_R2") (pin "1") (pinfunction "1_1") (pintype "passive"))
    )
    (net (code "30") (name "Net-(7_C3-Pad1)") (class "Default")
      (node (ref "7_C3") (pin "1") (pinfunction "1_1") (pintype "passive"))
      (node (ref "7_C4") (pin "2") (pinfunction "2_2") (pintype "passive"))
      (node (ref "7_R1") (pin "2") (pinfunction "2_2") (pintype "passive"))
      (node (ref "7_R3") (pin "1") (pinfunction "1_1") (pintype "passive"))
      (node (ref "7_R6") (pin "1") (pinfunction "1_1") (pintype "passive"))
    )
    (net (code "31") (name "Net-(7_C4-Pad1)") (class "Default")
      (node (ref "7_C4") (pin "1") (pinfunction "1_1") (pintype "passive"))
      (node (ref "7_R2") (pin "2") (pinfunction "2_2") (pintype "passive"))
      (node (ref "7_R4") (pin "1") (pinfunction "1_1") (pintype "passive"))
      (node (ref "7_R5") (pin "2") (pinfunction "2_2") (pintype "passive"))
    )
    (net (code "32") (name "Net-(8_C1-Pad+)") (class "Default")
      (node (ref "8_C1") (pin "+") (pinfunction "+_+") (pintype "passive"))
      (node (ref "8_R1") (pin "1") (pinfunction "1_1") (pintype "passive"))
    )
    (net (code "33") (name "Net-(8_C2-Pad+)") (class "Default")
      (node (ref "8_C2") (pin "+") (pinfunction "+_+") (pintype "passive"))
      (node (ref "8_R2") (pin "1") (pinfunction "1_1") (pintype "passive"))
    )
    (net (code "34") (name "Net-(8_C3-Pad1)") (class "Default")
      (node (ref "8_C3") (pin "1") (pinfunction "1_1") (pintype "passive"))
      (node (ref "8_C4") (pin "2") (pinfunction "2_2") (pintype "passive"))
      (node (ref "8_R1") (pin "2") (pinfunction "2_2") (pintype "passive"))
      (node (ref "8_R3") (pin "1") (pinfunction "1_1") (pintype "passive"))
      (node (ref "8_R6") (pin "1") (pinfunction "1_1") (pintype "passive"))
    )
    (net (code "35") (name "Net-(8_C4-Pad1)") (class "Default")
      (node (ref "8_C4") (pin "1") (pinfunction "1_1") (pintype "passive"))
      (node (ref "8_R2") (pin "2") (pinfunction "2_2") (pintype "passive"))
      (node (ref "8_R4") (pin "1") (pinfunction "1_1") (pintype "passive"))
      (node (ref "8_R5") (pin "2") (pinfunction "2_2") (pintype "passive"))
    )
    (net (code "36") (name "Net-(C2-Pad2)") (class "Default")
      (node (ref "C2") (pin "2") (pinfunction "2_2") (pintype "passive"))
      (node (ref "R15") (pin "2") (pinfunction "2_2") (pintype "passive"))
    )
    (net (code "37") (name "Net-(IC1A-+IN)") (class "Default")
      (node (ref "1_C5") (pin "2") (pinfunction "2_2") (pintype "passive"))
      (node (ref "1_R4") (pin "2") (pinfunction "2_2") (pintype "passive"))
      (node (ref "IC1") (pin "3") (pinfunction "+IN_3") (pintype "input"))
    )
    (net (code "38") (name "Net-(IC1A--IN)") (class "Default")
      (node (ref "1_R3") (pin "2") (pinfunction "2_2") (pintype "passive"))
      (node (ref "IC1") (pin "2") (pinfunction "-IN_2") (pintype "input"))
    )
    (net (code "39") (name "Net-(IC1A-OUT)") (class "Default")
      (node (ref "1_C3") (pin "2") (pinfunction "2_2") (pintype "passive"))
      (node (ref "1_R6") (pin "2") (pinfunction "2_2") (pintype "passive"))
      (node (ref "1_R7") (pin "1") (pinfunction "1_1") (pintype "passive"))
      (node (ref "IC1") (pin "1") (pinfunction "OUT_1") (pintype "output"))
    )
    (net (code "40") (name "Net-(IC1B-+IN)") (class "Default")
      (node (ref "2_C5") (pin "2") (pinfunction "2_2") (pintype "passive"))
      (node (ref "2_R4") (pin "2") (pinfunction "2_2") (pintype "passive"))
      (node (ref "IC1") (pin "5") (pinfunction "+IN_5") (pintype "input"))
    )
    (net (code "41") (name "Net-(IC1B--IN)") (class "Default")
      (node (ref "2_R3") (pin "2") (pinfunction "2_2") (pintype "passive"))
      (node (ref "IC1") (pin "6") (pinfunction "-IN_6") (pintype "input"))
    )
    (net (code "42") (name "Net-(IC1B-OUT)") (class "Default")
      (node (ref "2_C3") (pin "2") (pinfunction "2_2") (pintype "passive"))
      (node (ref "2_R6") (pin "2") (pinfunction "2_2") (pintype "passive"))
      (node (ref "2_R7") (pin "1") (pinfunction "1_1") (pintype "passive"))
      (node (ref "IC1") (pin "7") (pinfunction "OUT_7") (pintype "output"))
    )
    (net (code "43") (name "Net-(IC2-ADJ)") (class "Default")
      (node (ref "C34") (pin "+") (pinfunction "+_+") (pintype "passive"))
      (node (ref "IC2") (pin "1") (pinfunction "ADJ_1") (pintype "input"))
      (node (ref "R24") (pin "2") (pinfunction "2_2") (pintype "passive"))
      (node (ref "R25") (pin "1") (pinfunction "1_1") (pintype "passive"))
    )
    (net (code "44") (name "Net-(IC2-IN)") (class "Default")
      (node (ref "B1") (pin "+") (pinfunction "+_+") (pintype "passive"))
      (node (ref "C17") (pin "+") (pinfunction "+_+") (pintype "passive"))
      (node (ref "C19") (pin "1") (pinfunction "1_1") (pintype "passive"))
      (node (ref "C24") (pin "+") (pinfunction "+_+") (pintype "passive"))
      (node (ref "C26") (pin "1") (pinfunction "1_1") (pintype "passive"))
      (node (ref "D1") (pin "C") (pinfunction "C_C") (pintype "passive"))
      (node (ref "D6") (pin "C") (pinfunction "C_C") (pintype "passive"))
      (node (ref "IC2") (pin "3") (pinfunction "IN_3") (pintype "input"))
      (node (ref "IC7") (pin "3") (pinfunction "IN_3") (pintype "input"))
    )
    (net (code "45") (name "Net-(IC3-ADJ)") (class "Default")
      (node (ref "C33") (pin "-") (pinfunction "-_-") (pintype "passive"))
      (node (ref "IC3") (pin "1") (pinfunction "ADJ_1") (pintype "input"))
      (node (ref "R23") (pin "1") (pinfunction "1_1") (pintype "passive"))
      (node (ref "R26") (pin "2") (pinfunction "2_2") (pintype "passive"))
    )
    (net (code "46") (name "Net-(IC3-IN)") (class "Default")
      (node (ref "B1") (pin "-") (pinfunction "-_-") (pintype "passive"))
      (node (ref "C25") (pin "-") (pinfunction "-_-") (pintype "passive"))
      (node (ref "C27") (pin "2") (pinfunction "2_2") (pintype "passive"))
      (node (ref "D5") (pin "A") (pinfunction "A_A") (pintype "passive"))
      (node (ref "IC3") (pin "2") (pinfunction "IN_2") (pintype "input"))
    )
    (net (code "47") (name "Net-(IC4A-+IN)") (class "Default")
      (node (ref "3_C5") (pin "2") (pinfunction "2_2") (pintype "passive"))
      (node (ref "3_R4") (pin "2") (pinfunction "2_2") (pintype "passive"))
      (node (ref "IC4") (pin "3") (pinfunction "+IN_3") (pintype "input"))
    )
    (net (code "48") (name "Net-(IC4A--IN)") (class "Default")
      (node (ref "3_R3") (pin "2") (pinfunction "2_2") (pintype "passive"))
      (node (ref "IC4") (pin "2") (pinfunction "-IN_2") (pintype "input"))
    )
    (net (code "49") (name "Net-(IC4A-OUT)") (class "Default")
      (node (ref "3_C3") (pin "2") (pinfunction "2_2") (pintype "passive"))
      (node (ref "3_R6") (pin "2") (pinfunction "2_2") (pintype "passive"))
      (node (ref "3_R7") (pin "1") (pinfunction "1_1") (pintype "passive"))
      (node (ref "IC4") (pin "1") (pinfunction "OUT_1") (pintype "output"))
    )
    (net (code "50") (name "Net-(IC4B-+IN)") (class "Default")
      (node (ref "4_C5") (pin "2") (pinfunction "2_2") (pintype "passive"))
      (node (ref "4_R4") (pin "2") (pinfunction "2_2") (pintype "passive"))
      (node (ref "IC4") (pin "5") (pinfunction "+IN_5") (pintype "input"))
    )
    (net (code "51") (name "Net-(IC4B--IN)") (class "Default")
      (node (ref "4_R3") (pin "2") (pinfunction "2_2") (pintype "passive"))
      (node (ref "IC4") (pin "6") (pinfunction "-IN_6") (pintype "input"))
    )
    (net (code "52") (name "Net-(IC4B-OUT)") (class "Default")
      (node (ref "4_C3") (pin "2") (pinfunction "2_2") (pintype "passive"))
      (node (ref "4_R6") (pin "2") (pinfunction "2_2") (pintype "passive"))
      (node (ref "4_R7") (pin "1") (pinfunction "1_1") (pintype "passive"))
      (node (ref "IC4") (pin "7") (pinfunction "OUT_7") (pintype "output"))
    )
    (net (code "53") (name "Net-(IC5A-+IN)") (class "Default")
      (node (ref "5_C5") (pin "2") (pinfunction "2_2") (pintype "passive"))
      (node (ref "5_R4") (pin "2") (pinfunction "2_2") (pintype "passive"))
      (node (ref "IC5") (pin "3") (pinfunction "+IN_3") (pintype "input"))
    )
    (net (code "54") (name "Net-(IC5A--IN)") (class "Default")
      (node (ref "5_R3") (pin "2") (pinfunction "2_2") (pintype "passive"))
      (node (ref "IC5") (pin "2") (pinfunction "-IN_2") (pintype "input"))
    )
    (net (code "55") (name "Net-(IC5A-OUT)") (class "Default")
      (node (ref "5_C3") (pin "2") (pinfunction "2_2") (pintype "passive"))
      (node (ref "5_R6") (pin "2") (pinfunction "2_2") (pintype "passive"))
      (node (ref "5_R7") (pin "1") (pinfunction "1_1") (pintype "passive"))
      (node (ref "IC5") (pin "1") (pinfunction "OUT_1") (pintype "output"))
    )
    (net (code "56") (name "Net-(IC5B-+IN)") (class "Default")
      (node (ref "6_C5") (pin "2") (pinfunction "2_2") (pintype "passive"))
      (node (ref "6_R4") (pin "2") (pinfunction "2_2") (pintype "passive"))
      (node (ref "IC5") (pin "5") (pinfunction "+IN_5") (pintype "input"))
    )
    (net (code "57") (name "Net-(IC5B--IN)") (class "Default")
      (node (ref "6_R3") (pin "2") (pinfunction "2_2") (pintype "passive"))
      (node (ref "IC5") (pin "6") (pinfunction "-IN_6") (pintype "input"))
    )
    (net (code "58") (name "Net-(IC5B-OUT)") (class "Default")
      (node (ref "6_C3") (pin "2") (pinfunction "2_2") (pintype "passive"))
      (node (ref "6_R6") (pin "2") (pinfunction "2_2") (pintype "passive"))
      (node (ref "6_R7") (pin "1") (pinfunction "1_1") (pintype "passive"))
      (node (ref "IC5") (pin "7") (pinfunction "OUT_7") (pintype "output"))
    )
    (net (code "59") (name "Net-(IC6A-+IN)") (class "Default")
      (node (ref "7_C5") (pin "2") (pinfunction "2_2") (pintype "passive"))
      (node (ref "7_R4") (pin "2") (pinfunction "2_2") (pintype "passive"))
      (node (ref "IC6") (pin "3") (pinfunction "+IN_3") (pintype "input"))
    )
    (net (code "60") (name "Net-(IC6A--IN)") (class "Default")
      (node (ref "7_R3") (pin "2") (pinfunction "2_2") (pintype "passive"))
      (node (ref "IC6") (pin "2") (pinfunction "-IN_2") (pintype "input"))
    )
    (net (code "61") (name "Net-(IC6A-OUT)") (class "Default")
      (node (ref "7_C3") (pin "2") (pinfunction "2_2") (pintype "passive"))
      (node (ref "7_R6") (pin "2") (pinfunction "2_2") (pintype "passive"))
      (node (ref "7_R7") (pin "1") (pinfunction "1_1") (pintype "passive"))
      (node (ref "IC6") (pin "1") (pinfunction "OUT_1") (pintype "output"))
    )
    (net (code "62") (name "Net-(IC6B-+IN)") (class "Default")
      (node (ref "8_C5") (pin "2") (pinfunction "2_2") (pintype "passive"))
      (node (ref "8_R4") (pin "2") (pinfunction "2_2") (pintype "passive"))
      (node (ref "IC6") (pin "5") (pinfunction "+IN_5") (pintype "input"))
    )
    (net (code "63") (name "Net-(IC6B--IN)") (class "Default")
      (node (ref "8_R3") (pin "2") (pinfunction "2_2") (pintype "passive"))
      (node (ref "IC6") (pin "6") (pinfunction "-IN_6") (pintype "input"))
    )
    (net (code "64") (name "Net-(IC6B-OUT)") (class "Default")
      (node (ref "8_C3") (pin "2") (pinfunction "2_2") (pintype "passive"))
      (node (ref "8_R6") (pin "2") (pinfunction "2_2") (pintype "passive"))
      (node (ref "8_R7") (pin "1") (pinfunction "1_1") (pintype "passive"))
      (node (ref "IC6") (pin "7") (pinfunction "OUT_7") (pintype "output"))
    )
    (net (code "65") (name "Net-(IC7-ADJ)") (class "Default")
      (node (ref "IC7") (pin "1") (pinfunction "ADJ_1") (pintype "input"))
      (node (ref "R10") (pin "2") (pinfunction "2_2") (pintype "passive"))
      (node (ref "R12") (pin "1") (pinfunction "1_1") (pintype "passive"))
    )
    (net (code "66") (name "Net-(LCDC-S)") (class "Default")
      (node (ref "LCD") (pin "3") (pinfunction "S_3") (pintype "passive"))
      (node (ref "R39") (pin "1") (pinfunction "1_1") (pintype "passive"))
      (node (ref "U$1") (pin "18") (pinfunction "I2C_SDA_18") (pintype "bidirectional"))
      (node (ref "U1") (pin "20") (pinfunction "MD/SDA/DEMP_20") (pintype "bidirectional"))
    )
    (net (code "67") (name "Net-(LCDD-S)") (class "Default")
      (node (ref "LCD") (pin "4") (pinfunction "S_4") (pintype "passive"))
      (node (ref "R38") (pin "1") (pinfunction "1_1") (pintype "passive"))
      (node (ref "U$1") (pin "17") (pinfunction "I2C_SCL_17") (pintype "bidirectional"))
      (node (ref "U1") (pin "21") (pinfunction "MC/SCL/FMT_21") (pintype "input"))
    )
    (net (code "68") (name "Net-(LED1-PadA)") (class "Default")
      (node (ref "LED1") (pin "A") (pinfunction "A_A") (pintype "passive"))
      (node (ref "R11") (pin "1") (pinfunction "1_1") (pintype "passive"))
    )
    (net (code "69") (name "Net-(LED1-PadC)") (class "Default")
      (node (ref "LED1") (pin "C") (pinfunction "C_C") (pintype "passive"))
      (node (ref "Q2") (pin "D") (pinfunction "D_D") (pintype "passive"))
    )
    (net (code "70") (name "Net-(OUT1B-S)") (class "Default")
      (node (ref "1_R7") (pin "2") (pinfunction "2_2") (pintype "passive"))
      (node (ref "OUT1") (pin "2") (pinfunction "S_2") (pintype "passive"))
    )
    (net (code "71") (name "Net-(OUT2B-S)") (class "Default")
      (node (ref "2_R7") (pin "2") (pinfunction "2_2") (pintype "passive"))
      (node (ref "OUT2") (pin "2") (pinfunction "S_2") (pintype "passive"))
    )
    (net (code "72") (name "Net-(OUT3B-S)") (class "Default")
      (node (ref "3_R7") (pin "2") (pinfunction "2_2") (pintype "passive"))
      (node (ref "OUT3") (pin "2") (pinfunction "S_2") (pintype "passive"))
    )
    (net (code "73") (name "Net-(OUT4B-S)") (class "Default")
      (node (ref "4_R7") (pin "2") (pinfunction "2_2") (pintype "passive"))
      (node (ref "OUT4") (pin "2") (pinfunction "S_2") (pintype "passive"))
    )
    (net (code "74") (name "Net-(OUT5B-S)") (class "Default")
      (node (ref "5_R7") (pin "2") (pinfunction "2_2") (pintype "passive"))
      (node (ref "OUT5") (pin "2") (pinfunction "S_2") (pintype "passive"))
    )
    (net (code "75") (name "Net-(OUT6B-S)") (class "Default")
      (node (ref "6_R7") (pin "2") (pinfunction "2_2") (pintype "passive"))
      (node (ref "OUT6") (pin "2") (pinfunction "S_2") (pintype "passive"))
    )
    (net (code "76") (name "Net-(OUT7B-S)") (class "Default")
      (node (ref "7_R7") (pin "2") (pinfunction "2_2") (pintype "passive"))
      (node (ref "OUT7") (pin "2") (pinfunction "S_2") (pintype "passive"))
    )
    (net (code "77") (name "Net-(OUT8B-S)") (class "Default")
      (node (ref "8_R7") (pin "2") (pinfunction "2_2") (pintype "passive"))
      (node (ref "OUT8") (pin "2") (pinfunction "S_2") (pintype "passive"))
    )
    (net (code "78") (name "Net-(P1-OUT)") (class "Default")
      (node (ref "P1") (pin "1") (pinfunction "OUT_1") (pintype "output"))
      (node (ref "U2") (pin "20") (pinfunction "RXIN_20") (pintype "input"))
    )
    (net (code "79") (name "Net-(P1-VDD)") (class "Default")
      (node (ref "C10") (pin "2") (pinfunction "2_2") (pintype "passive"))
      (node (ref "C16") (pin "+") (pinfunction "+_+") (pintype "passive"))
      (node (ref "L1") (pin "1") (pinfunction "1_1") (pintype "passive"))
      (node (ref "P1") (pin "3") (pinfunction "VDD_3") (pintype "power_in"))
    )
    (net (code "80") (name "Net-(U$1-ACLKR)") (class "Default")
      (node (ref "R31") (pin "1") (pinfunction "1_1") (pintype "passive"))
      (node (ref "U$1") (pin "12") (pinfunction "ACLKR_12") (pintype "bidirectional"))
    )
    (net (code "81") (name "Net-(U$1-ACLKX)") (class "Default")
      (node (ref "R36") (pin "1") (pinfunction "1_1") (pintype "passive"))
      (node (ref "U$1") (pin "31") (pinfunction "ACLKX_31") (pintype "bidirectional"))
    )
    (net (code "82") (name "Net-(U$1-AHCLKR)") (class "Default")
      (node (ref "R4") (pin "1") (pinfunction "1_1") (pintype "passive"))
      (node (ref "U$1") (pin "25") (pinfunction "AHCLKX_25") (pintype "bidirectional"))
      (node (ref "U$1") (pin "28") (pinfunction "AHCLKR_28") (pintype "bidirectional"))
    )
    (net (code "83") (name "Net-(U$1-DECODING_LED(GPIO0_7))") (class "Default")
      (node (ref "Q2") (pin "G") (pinfunction "G_G") (pintype "passive"))
      (node (ref "U$1") (pin "42") (pinfunction "DECODING_LED(GPIO0_7)_42") (pintype "output"))
    )
    (net (code "84") (name "Net-(U$1-DIN)") (class "Default")
      (node (ref "R32") (pin "1") (pinfunction "1_1") (pintype "passive"))
      (node (ref "U$1") (pin "30") (pinfunction "DIN_30") (pintype "bidirectional"))
    )
    (net (code "85") (name "Net-(U$1-DIR_AUDIO(GPIO1_19))") (class "Default")
      (node (ref "U$1") (pin "16") (pinfunction "DIR_AUDIO(GPIO1_19)_16") (pintype "input"))
      (node (ref "U2") (pin "1") (pinfunction "AUDIO_1") (pintype "output"))
    )
    (net (code "86") (name "Net-(U$1-DOUT)") (class "Default")
      (node (ref "R37") (pin "1") (pinfunction "1_1") (pintype "passive"))
      (node (ref "U$1") (pin "41") (pinfunction "DOUT_41") (pintype "bidirectional"))
    )
    (net (code "87") (name "Net-(U$1-EEPROM_I2C_SCL)") (class "Default")
      (node (ref "R8") (pin "1") (pinfunction "1_1") (pintype "passive"))
      (node (ref "U$1") (pin "19") (pinfunction "EEPROM_I2C_SCL_19") (pintype "bidirectional"))
      (node (ref "U3") (pin "6") (pinfunction "SCL_6") (pintype "bidirectional"))
    )
    (net (code "88") (name "Net-(U$1-EEPROM_I2C_SDA)") (class "Default")
      (node (ref "R2") (pin "1") (pinfunction "1_1") (pintype "passive"))
      (node (ref "U$1") (pin "20") (pinfunction "EEPROM_I2C_SDA_20") (pintype "bidirectional"))
      (node (ref "U3") (pin "5") (pinfunction "SDA_5") (pintype "bidirectional"))
    )
    (net (code "89") (name "Net-(U$1-FSR)") (class "Default")
      (node (ref "R30") (pin "1") (pinfunction "1_1") (pintype "passive"))
      (node (ref "U$1") (pin "27") (pinfunction "FSR_27") (pintype "bidirectional"))
    )
    (net (code "90") (name "Net-(U$1-FSX)") (class "Default")
      (node (ref "R35") (pin "1") (pinfunction "1_1") (pintype "passive"))
      (node (ref "U$1") (pin "29") (pinfunction "FSX_29") (pintype "bidirectional"))
    )
    (net (code "91") (name "Net-(U$1-RESET(GPIO1_16))") (class "Default")
      (node (ref "U$1") (pin "15") (pinfunction "RESET(GPIO1_16)_15") (pintype "output"))
      (node (ref "U1") (pin "15") (pinfunction "RST_15") (pintype "input"))
      (node (ref "U2") (pin "21") (pinfunction "RST_21") (pintype "input"))
    )
    (net (code "92") (name "Net-(U1-AMUTEI)") (class "Default")
      (node (ref "R5") (pin "2") (pinfunction "2_2") (pintype "passive"))
      (node (ref "U1") (pin "18") (pinfunction "AMUTEI_18") (pintype "input"))
    )
    (net (code "93") (name "Net-(U1-AMUTEO)") (class "Default")
      (node (ref "R6") (pin "2") (pinfunction "2_2") (pintype "passive"))
      (node (ref "U1") (pin "19") (pinfunction "AMUTEO_19") (pintype "output"))
    )
    (net (code "94") (name "Net-(U1-BCK)") (class "Default")
      (node (ref "R36") (pin "2") (pinfunction "2_2") (pintype "passive"))
      (node (ref "U1") (pin "7") (pinfunction "BCK_7") (pintype "input"))
    )
    (net (code "95") (name "Net-(U1-DIN1)") (class "Default")
      (node (ref "R37") (pin "2") (pinfunction "2_2") (pintype "passive"))
      (node (ref "U1") (pin "8") (pinfunction "DIN1_8") (pintype "input"))
    )
    (net (code "96") (name "Net-(U1-LRCK)") (class "Default")
      (node (ref "R35") (pin "2") (pinfunction "2_2") (pintype "passive"))
      (node (ref "U1") (pin "6") (pinfunction "LRCK_6") (pintype "input"))
    )
    (net (code "97") (name "Net-(U1-MODE)") (class "Default")
      (node (ref "R7") (pin "2") (pinfunction "2_2") (pintype "passive"))
      (node (ref "U1") (pin "24") (pinfunction "MODE_24") (pintype "input"))
    )
    (net (code "98") (name "Net-(U1-SCKI)") (class "Default")
      (node (ref "R4") (pin "2") (pinfunction "2_2") (pintype "passive"))
      (node (ref "U1") (pin "14") (pinfunction "SCKI_14") (pintype "input"))
      (node (ref "U2") (pin "4") (pinfunction "SCKO_4") (pintype "output"))
    )
    (net (code "99") (name "Net-(U1-TEST{slash}ADR1{slash}RSV)") (class "Default")
      (node (ref "R3") (pin "2") (pinfunction "2_2") (pintype "passive"))
      (node (ref "U1") (pin "23") (pinfunction "TEST/ADR1/RSV_23") (pintype "bidirectional"))
    )
    (net (code "100") (name "Net-(U1-VCOM)") (class "Default")
      (node (ref "C3") (pin "+") (pinfunction "+_+") (pintype "passive"))
      (node (ref "U1") (pin "26") (pinfunction "VCOM_26") (pintype "power_in"))
    )
    (net (code "101") (name "Net-(U1-VOUT1+)") (class "Default")
      (node (ref "1_C1") (pin "-") (pinfunction "-_-") (pintype "passive"))
      (node (ref "U1") (pin "43") (pinfunction "VOUT1+_43") (pintype "output"))
    )
    (net (code "102") (name "Net-(U1-VOUT1-)") (class "Default")
      (node (ref "1_C2") (pin "-") (pinfunction "-_-") (pintype "passive"))
      (node (ref "U1") (pin "44") (pinfunction "VOUT1-_44") (pintype "output"))
    )
    (net (code "103") (name "Net-(U1-VOUT2+)") (class "Default")
      (node (ref "2_C1") (pin "-") (pinfunction "-_-") (pintype "passive"))
      (node (ref "U1") (pin "41") (pinfunction "VOUT2+_41") (pintype "output"))
    )
    (net (code "104") (name "Net-(U1-VOUT2-)") (class "Default")
      (node (ref "2_C2") (pin "-") (pinfunction "-_-") (pintype "passive"))
      (node (ref "U1") (pin "42") (pinfunction "VOUT2-_42") (pintype "output"))
    )
    (net (code "105") (name "Net-(U1-VOUT3+)") (class "Default")
      (node (ref "3_C1") (pin "-") (pinfunction "-_-") (pintype "passive"))
      (node (ref "U1") (pin "39") (pinfunction "VOUT3+_39") (pintype "output"))
    )
    (net (code "106") (name "Net-(U1-VOUT3-)") (class "Default")
      (node (ref "3_C2") (pin "-") (pinfunction "-_-") (pintype "passive"))
      (node (ref "U1") (pin "40") (pinfunction "VOUT3-_40") (pintype "output"))
    )
    (net (code "107") (name "Net-(U1-VOUT4+)") (class "Default")
      (node (ref "4_C1") (pin "-") (pinfunction "-_-") (pintype "passive"))
      (node (ref "U1") (pin "37") (pinfunction "VOUT4+_37") (pintype "output"))
    )
    (net (code "108") (name "Net-(U1-VOUT4-)") (class "Default")
      (node (ref "4_C2") (pin "-") (pinfunction "-_-") (pintype "passive"))
      (node (ref "U1") (pin "38") (pinfunction "VOUT4-_38") (pintype "output"))
    )
    (net (code "109") (name "Net-(U1-VOUT5+)") (class "Default")
      (node (ref "5_C1") (pin "-") (pinfunction "-_-") (pintype "passive"))
      (node (ref "U1") (pin "35") (pinfunction "VOUT5+_35") (pintype "output"))
    )
    (net (code "110") (name "Net-(U1-VOUT5-)") (class "Default")
      (node (ref "5_C2") (pin "-") (pinfunction "-_-") (pintype "passive"))
      (node (ref "U1") (pin "36") (pinfunction "VOUT5-_36") (pintype "output"))
    )
    (net (code "111") (name "Net-(U1-VOUT6+)") (class "Default")
      (node (ref "6_C1") (pin "-") (pinfunction "-_-") (pintype "passive"))
      (node (ref "U1") (pin "33") (pinfunction "VOUT6+_33") (pintype "output"))
    )
    (net (code "112") (name "Net-(U1-VOUT6-)") (class "Default")
      (node (ref "6_C2") (pin "-") (pinfunction "-_-") (pintype "passive"))
      (node (ref "U1") (pin "34") (pinfunction "VOUT6-_34") (pintype "output"))
    )
    (net (code "113") (name "Net-(U1-VOUT7+)") (class "Default")
      (node (ref "7_C1") (pin "-") (pinfunction "-_-") (pintype "passive"))
      (node (ref "U1") (pin "31") (pinfunction "VOUT7+_31") (pintype "output"))
    )
    (net (code "114") (name "Net-(U1-VOUT7-)") (class "Default")
      (node (ref "7_C2") (pin "-") (pinfunction "-_-") (pintype "passive"))
      (node (ref "U1") (pin "32") (pinfunction "VOUT7-_32") (pintype "output"))
    )
    (net (code "115") (name "Net-(U1-VOUT8+)") (class "Default")
      (node (ref "8_C1") (pin "-") (pinfunction "-_-") (pintype "passive"))
      (node (ref "U1") (pin "29") (pinfunction "VOUT8+_29") (pintype "output"))
    )
    (net (code "116") (name "Net-(U1-VOUT8-)") (class "Default")
      (node (ref "8_C2") (pin "-") (pinfunction "-_-") (pintype "passive"))
      (node (ref "U1") (pin "30") (pinfunction "VOUT8-_30") (pintype "output"))
    )
    (net (code "117") (name "Net-(U2-BCKO)") (class "Default")
      (node (ref "R31") (pin "2") (pinfunction "2_2") (pintype "passive"))
      (node (ref "U2") (pin "11") (pinfunction "BCKO_11") (pintype "output"))
    )
    (net (code "118") (name "Net-(U2-DOUT)") (class "Default")
      (node (ref "R32") (pin "2") (pinfunction "2_2") (pintype "passive"))
      (node (ref "U2") (pin "12") (pinfunction "DOUT_12") (pintype "output"))
    )
    (net (code "119") (name "Net-(U2-FILT)") (class "Default")
      (node (ref "C1") (pin "2") (pinfunction "2_2") (pintype "passive"))
      (node (ref "R15") (pin "1") (pinfunction "1_1") (pintype "passive"))
      (node (ref "U2") (pin "22") (pinfunction "FILT_22") (pintype "bidirectional"))
    )
    (net (code "120") (name "Net-(U2-FMT0)") (class "Default")
      (node (ref "JP1") (pin "2") (pinfunction "2_2") (pintype "passive"))
      (node (ref "U2") (pin "25") (pinfunction "FMT0_25") (pintype "input"))
    )
    (net (code "121") (name "Net-(U2-FMT1)") (class "Default")
      (node (ref "JP1") (pin "1") (pinfunction "1_1") (pintype "passive"))
      (node (ref "U2") (pin "26") (pinfunction "FMT1_26") (pintype "input"))
    )
    (net (code "122") (name "Net-(U2-LRCKO)") (class "Default")
      (node (ref "R30") (pin "2") (pinfunction "2_2") (pintype "passive"))
      (node (ref "U2") (pin "10") (pinfunction "LRCKO_10") (pintype "output"))
    )
    (net (code "123") (name "Net-(U3-A2)") (class "Default")
      (node (ref "R9") (pin "1") (pinfunction "1_1") (pintype "passive"))
      (node (ref "U3") (pin "3") (pinfunction "A2_3") (pintype "input"))
    )
    (net (code "124") (name "Net-(X1A-KL)") (class "Default")
      (node (ref "B1") (pin "AC1") (pinfunction "AC1_AC1") (pintype "passive"))
      (node (ref "X1") (pin "1") (pinfunction "KL_1") (pintype "passive"))
    )
    (net (code "125") (name "Net-(X1D-KL)") (class "Default")
      (node (ref "B1") (pin "AC2") (pinfunction "AC2_AC2") (pintype "passive"))
      (node (ref "X1") (pin "4") (pinfunction "KL_4") (pintype "passive"))
    )
    (net (code "126") (name "V+") (class "Default")
      (node (ref "C12") (pin "+") (pinfunction "+_+") (pintype "passive"))
      (node (ref "C13") (pin "+") (pinfunction "+_+") (pintype "passive"))
      (node (ref "C14") (pin "+") (pinfunction "+_+") (pintype "passive"))
      (node (ref "C28") (pin "+") (pinfunction "+_+") (pintype "passive"))
      (node (ref "C31") (pin "1") (pinfunction "1_1") (pintype "passive"))
      (node (ref "C32") (pin "1") (pinfunction "1_1") (pintype "passive"))
      (node (ref "C40") (pin "1") (pinfunction "1_1") (pintype "passive"))
      (node (ref "C8") (pin "1") (pinfunction "1_1") (pintype "passive"))
      (node (ref "C9") (pin "1") (pinfunction "1_1") (pintype "passive"))
      (node (ref "D6") (pin "A") (pinfunction "A_A") (pintype "passive"))
      (node (ref "D7") (pin "C") (pinfunction "C_C") (pintype "passive"))
      (node (ref "IC2") (pin "2") (pinfunction "OUT_2") (pintype "passive"))
      (node (ref "R1") (pin "1") (pinfunction "1_1") (pintype "passive"))
      (node (ref "R25") (pin "2") (pinfunction "2_2") (pintype "passive"))
    )
    (net (code "127") (name "V-") (class "Default")
      (node (ref "C12") (pin "-") (pinfunction "-_-") (pintype "passive"))
      (node (ref "C13") (pin "-") (pinfunction "-_-") (pintype "passive"))
      (node (ref "C14") (pin "-") (pinfunction "-_-") (pintype "passive"))
      (node (ref "C29") (pin "-") (pinfunction "-_-") (pintype "passive"))
      (node (ref "C30") (pin "2") (pinfunction "2_2") (pintype "passive"))
      (node (ref "C32") (pin "2") (pinfunction "2_2") (pintype "passive"))
      (node (ref "C40") (pin "2") (pinfunction "2_2") (pintype "passive"))
      (node (ref "C8") (pin "2") (pinfunction "2_2") (pintype "passive"))
      (node (ref "C9") (pin "2") (pinfunction "2_2") (pintype "passive"))
      (node (ref "D5") (pin "C") (pinfunction "C_C") (pintype "passive"))
      (node (ref "D8") (pin "A") (pinfunction "A_A") (pintype "passive"))
      (node (ref "IC3") (pin "3") (pinfunction "OUT_3") (pintype "passive"))
      (node (ref "R26") (pin "1") (pinfunction "1_1") (pintype "passive"))
    )
    (net (code "128") (name "VCC") (class "Default")
      (node (ref "C4") (pin "2") (pinfunction "2_2") (pintype "passive"))
      (node (ref "C6") (pin "1") (pinfunction "1_1") (pintype "passive"))
      (node (ref "R1") (pin "2") (pinfunction "2_2") (pintype "passive"))
      (node (ref "U1") (pin "25") (pinfunction "VCC1_25") (pintype "power_in"))
      (node (ref "U1") (pin "47") (pinfunction "VCC2_47") (pintype "power_in"))
    )
    (net (code "129") (name "VDD") (class "Default")
      (node (ref "C11") (pin "2") (pinfunction "2_2") (pintype "passive"))
      (node (ref "C15") (pin "1") (pinfunction "1_1") (pintype "passive"))
      (node (ref "C5") (pin "2") (pinfunction "2_2") (pintype "passive"))
      (node (ref "C7") (pin "+") (pinfunction "+_+") (pintype "passive"))
      (node (ref "JP1") (pin "3") (pinfunction "3_3") (pintype "passive"))
      (node (ref "JP1") (pin "4") (pinfunction "4_4") (pintype "passive"))
      (node (ref "L1") (pin "2") (pinfunction "2_2") (pintype "passive"))
      (node (ref "R11") (pin "2") (pinfunction "2_2") (pintype "passive"))
      (node (ref "R2") (pin "2") (pinfunction "2_2") (pintype "passive"))
      (node (ref "R3") (pin "1") (pinfunction "1_1") (pintype "passive"))
      (node (ref "R38") (pin "2") (pinfunction "2_2") (pintype "passive"))
      (node (ref "R39") (pin "2") (pinfunction "2_2") (pintype "passive"))
      (node (ref "R5") (pin "1") (pinfunction "1_1") (pintype "passive"))
      (node (ref "R6") (pin "1") (pinfunction "1_1") (pintype "passive"))
      (node (ref "R8") (pin "2") (pinfunction "2_2") (pintype "passive"))
      (node (ref "R9") (pin "2") (pinfunction "2_2") (pintype "passive"))
      (node (ref "U$1") (pin "3") (pinfunction "3.3V_3") (pintype "power_in"))
      (node (ref "U$1") (pin "4") (pinfunction "3.3V_4") (pintype "power_in"))
      (node (ref "U1") (pin "12") (pinfunction "VDD_12") (pintype "power_in"))
      (node (ref "U2") (pin "13") (pinfunction "PSCK0_13") (pintype "input"))
      (node (ref "U2") (pin "14") (pinfunction "PSCK1_14") (pintype "input"))
      (node (ref "U2") (pin "24") (pinfunction "VCC_24") (pintype "power_in"))
      (node (ref "U2") (pin "5") (pinfunction "VDD_5") (pintype "power_in"))
      (node (ref "U3") (pin "8") (pinfunction "VCC_8") (pintype "power_in"))
    )
    (net (code "130") (name "unconnected-(U1-MS{slash}ADR0{slash}RSV-Pad22)") (class "Default")
      (node (ref "U1") (pin "22") (pinfunction "MS/ADR0/RSV_22") (pintype "input"))
    )
    (net (code "131") (name "unconnected-(U1-RSV1-Pad2)") (class "Default")
      (node (ref "U1") (pin "2") (pinfunction "RSV1_2") (pintype "bidirectional"))
    )
    (net (code "132") (name "unconnected-(U1-RSV1-Pad4)") (class "Default")
      (node (ref "U1") (pin "4") (pinfunction "RSV1_4") (pintype "bidirectional"))
    )
    (net (code "133") (name "unconnected-(U1-RSV2-Pad1)") (class "Default")
      (node (ref "U1") (pin "1") (pinfunction "RSV2_1") (pintype "bidirectional"))
    )
    (net (code "134") (name "unconnected-(U1-RSV2-Pad3)") (class "Default")
      (node (ref "U1") (pin "3") (pinfunction "RSV2_3") (pintype "bidirectional"))
    )
    (net (code "135") (name "unconnected-(U1-RSV2-Pad5)") (class "Default")
      (node (ref "U1") (pin "5") (pinfunction "RSV2_5") (pintype "bidirectional"))
    )
    (net (code "136") (name "unconnected-(U1-RSV2-Pad28)") (class "Default")
      (node (ref "U1") (pin "28") (pinfunction "RSV2_28") (pintype "bidirectional"))
    )
    (net (code "137") (name "unconnected-(U1-RSV2-Pad45)") (class "Default")
      (node (ref "U1") (pin "45") (pinfunction "RSV2_45") (pintype "bidirectional"))
    )
    (net (code "138") (name "unconnected-(U1-RSV2-Pad48)") (class "Default")
      (node (ref "U1") (pin "48") (pinfunction "RSV2_48") (pintype "bidirectional"))
    )
    (net (code "139") (name "unconnected-(U1-ZERO1-Pad16)") (class "Default")
      (node (ref "U1") (pin "16") (pinfunction "ZERO1_16") (pintype "output"))
    )
    (net (code "140") (name "unconnected-(U1-ZERO2-Pad17)") (class "Default")
      (node (ref "U1") (pin "17") (pinfunction "ZERO2_17") (pintype "output"))
    )
    (net (code "141") (name "unconnected-(U2-BFRAME-Pad18)") (class "Default")
      (node (ref "U2") (pin "18") (pinfunction "BFRAME_18") (pintype "bidirectional"))
    )
    (net (code "142") (name "unconnected-(U2-CKSEL-Pad28)") (class "Default")
      (node (ref "U2") (pin "28") (pinfunction "CKSEL_28") (pintype "input"))
    )
    (net (code "143") (name "unconnected-(U2-CLKST-Pad9)") (class "Default")
      (node (ref "U2") (pin "9") (pinfunction "CLKST_9") (pintype "output"))
    )
    (net (code "144") (name "unconnected-(U2-COUT-Pad15)") (class "Default")
      (node (ref "U2") (pin "15") (pinfunction "COUT_15") (pintype "output"))
    )
    (net (code "145") (name "unconnected-(U2-EMPH-Pad17)") (class "Default")
      (node (ref "U2") (pin "17") (pinfunction "EMPH_17") (pintype "output"))
    )
    (net (code "146") (name "unconnected-(U2-ERROR-Pad27)") (class "Default")
      (node (ref "U2") (pin "27") (pinfunction "ERROR_27") (pintype "output"))
    )
    (net (code "147") (name "unconnected-(U2-FSOUT0-Pad2)") (class "Default")
      (node (ref "U2") (pin "2") (pinfunction "FSOUT0_2") (pintype "output"))
    )
    (net (code "148") (name "unconnected-(U2-FSOUT1-Pad3)") (class "Default")
      (node (ref "U2") (pin "3") (pinfunction "FSOUT1_3") (pintype "output"))
    )
    (net (code "149") (name "unconnected-(U2-UOUT-Pad16)") (class "Default")
      (node (ref "U2") (pin "16") (pinfunction "UOUT_16") (pintype "output"))
    )
    (net (code "150") (name "unconnected-(U2-XTO-Pad7)") (class "Default")
      (node (ref "U2") (pin "7") (pinfunction "XTO_7") (pintype "output"))
    )
    (net (code "151") (name "unconnected-(U3-A0-Pad1)") (class "Default")
      (node (ref "U3") (pin "1") (pinfunction "A0_1") (pintype "input"))
    )
    (net (code "152") (name "unconnected-(U3-A1-Pad2)") (class "Default")
      (node (ref "U3") (pin "2") (pinfunction "A1_2") (pintype "input"))
    )
    (net (code "153") (name "unconnected-(U3-WP-Pad7)") (class "Default")
      (node (ref "U3") (pin "7") (pinfunction "WP_7") (pintype "input"))
    )
  )
)
